# 1203_05.net
KiCad netlist of a schematic drawn in EAGLE
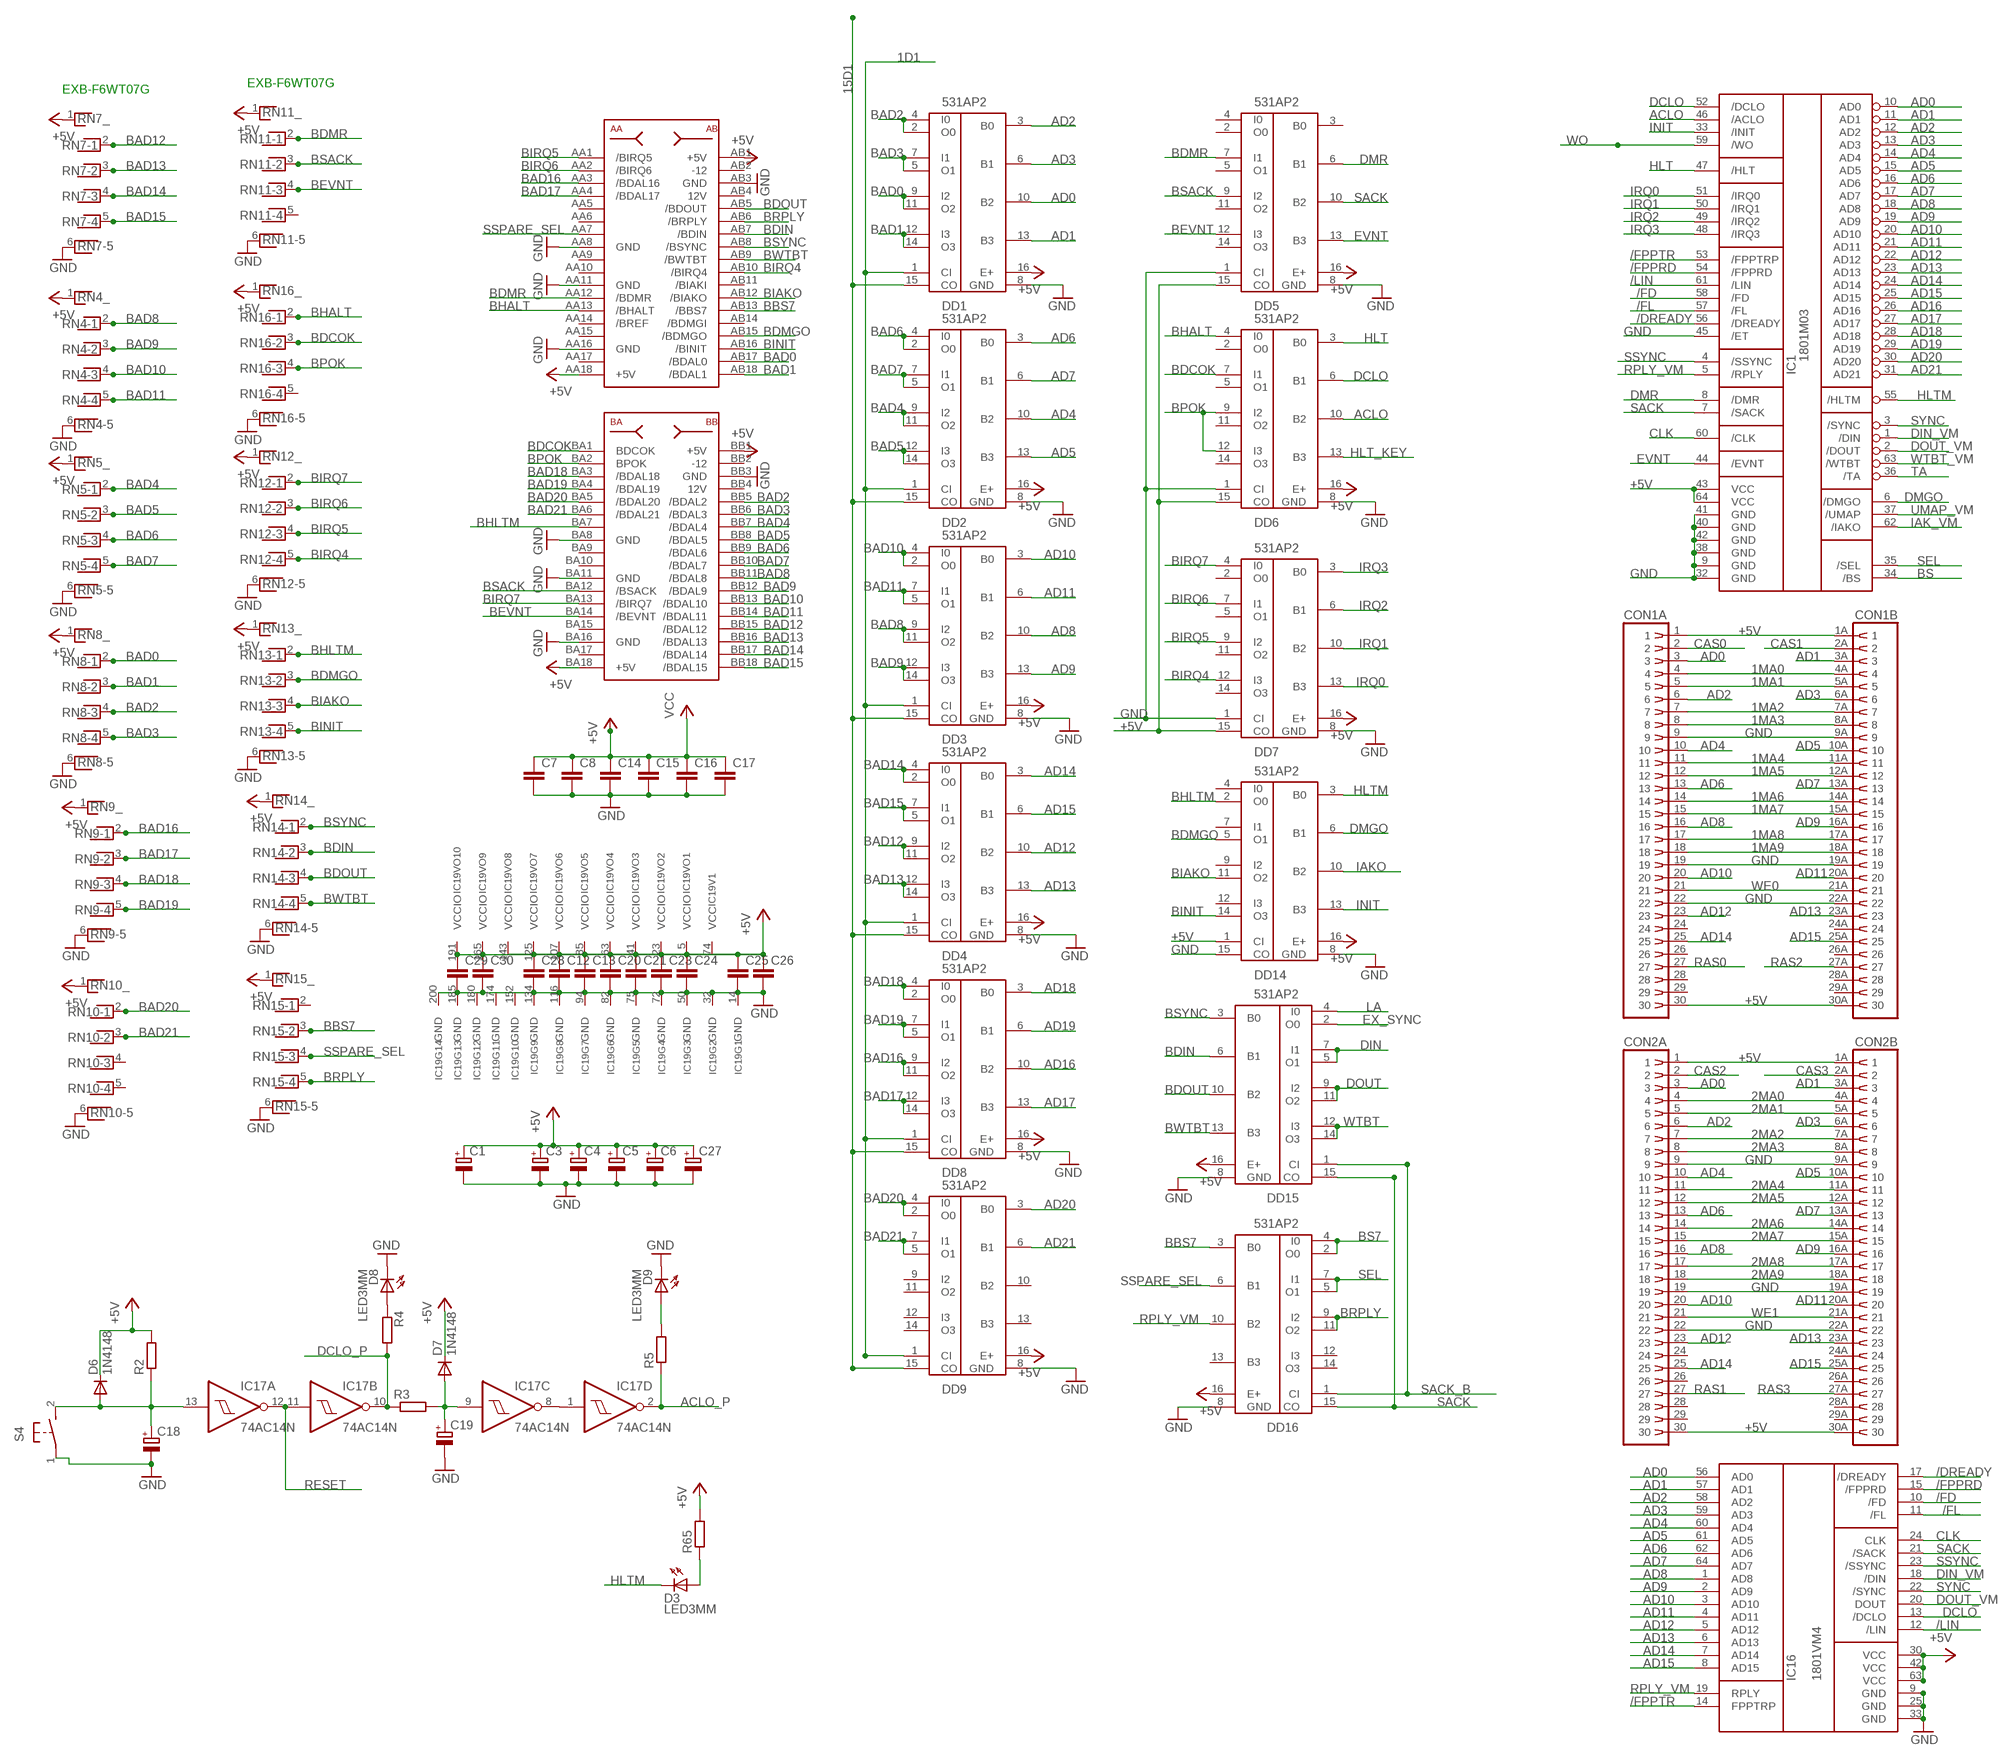
[diagram p0: schematic, sheet 1, part 1 of 2]
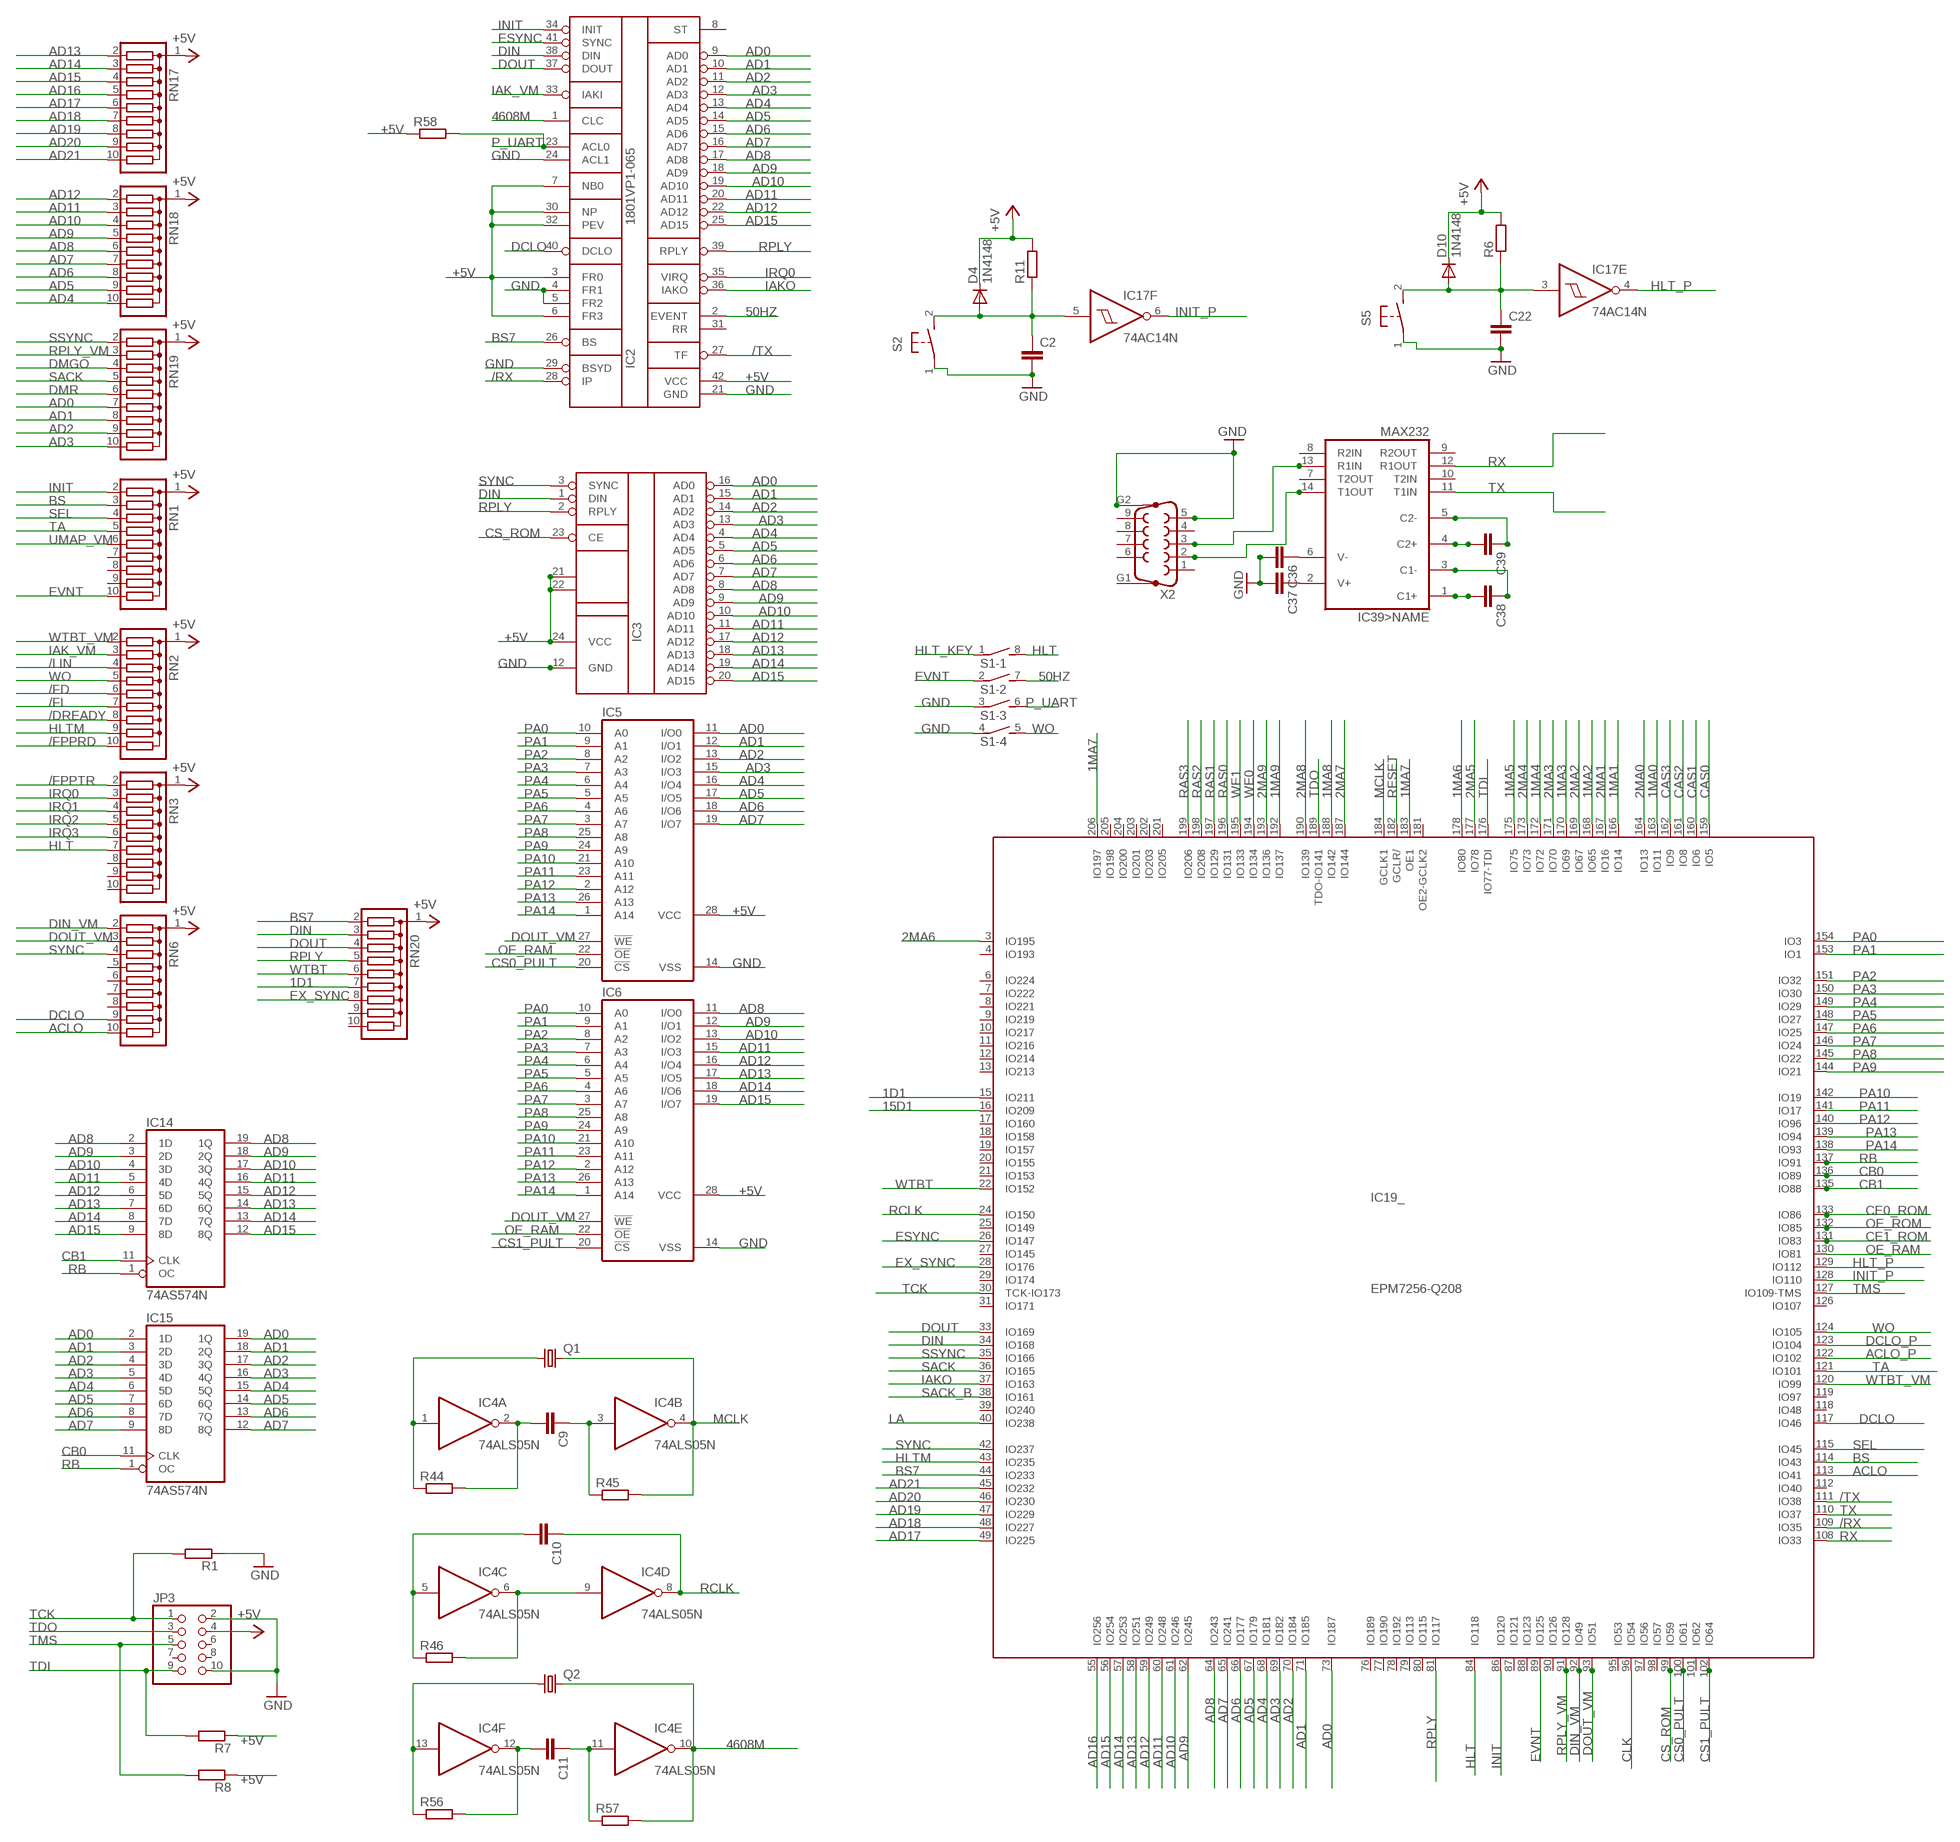
[diagram p1: schematic, sheet 1, part 2 of 2]

(export (version "E")
  (design (tool "Eeschema 10.0.6"))
  (components
    (comp (ref "C1")
      (value "CPOL-EUCT6032")
      (footprint "eagle-import:CT6032")
      (libsource (lib "eagle-import") (part "CPOL-EUCT6032"))
    )
    (comp (ref "C2")
      (value "C-EU050-024X044")
      (footprint "eagle-import:C050-024X044")
      (libsource (lib "eagle-import") (part "C-EU050-024X044"))
    )
    (comp (ref "C3")
      (value "CPOL-EUCT6032")
      (footprint "eagle-import:CT6032")
      (libsource (lib "eagle-import") (part "CPOL-EUCT6032"))
    )
    (comp (ref "C4")
      (value "CPOL-EUCT6032")
      (footprint "eagle-import:CT6032")
      (libsource (lib "eagle-import") (part "CPOL-EUCT6032"))
    )
    (comp (ref "C5")
      (value "CPOL-EUB45181A")
      (footprint "eagle-import:B45181A")
      (libsource (lib "eagle-import") (part "CPOL-EUB45181A"))
    )
    (comp (ref "C6")
      (value "CPOL-EUCT6032")
      (footprint "eagle-import:CT6032")
      (libsource (lib "eagle-import") (part "CPOL-EUCT6032"))
    )
    (comp (ref "C7")
      (value "C-EU050-024X044")
      (footprint "eagle-import:C050-024X044")
      (libsource (lib "eagle-import") (part "C-EU050-024X044"))
    )
    (comp (ref "C8")
      (value "C-EU050-024X044")
      (footprint "eagle-import:C050-024X044")
      (libsource (lib "eagle-import") (part "C-EU050-024X044"))
    )
    (comp (ref "C9")
      (value "C-EUC0805")
      (footprint "eagle-import:C0805")
      (libsource (lib "eagle-import") (part "C-EUC0805"))
    )
    (comp (ref "C10")
      (value "C-EU025-024X044")
      (footprint "eagle-import:C025-024X044")
      (libsource (lib "eagle-import") (part "C-EU025-024X044"))
    )
    (comp (ref "C11")
      (value "C-EUC0805")
      (footprint "eagle-import:C0805")
      (libsource (lib "eagle-import") (part "C-EUC0805"))
    )
    (comp (ref "C12")
      (value "C-EUC0805")
      (footprint "eagle-import:C0805")
      (libsource (lib "eagle-import") (part "C-EUC0805"))
    )
    (comp (ref "C13")
      (value "C-EUC0805")
      (footprint "eagle-import:C0805")
      (libsource (lib "eagle-import") (part "C-EUC0805"))
    )
    (comp (ref "C14")
      (value "C-EU050-024X044")
      (footprint "eagle-import:C050-024X044")
      (libsource (lib "eagle-import") (part "C-EU050-024X044"))
    )
    (comp (ref "C15")
      (value "C-EU050-024X044")
      (footprint "eagle-import:C050-024X044")
      (libsource (lib "eagle-import") (part "C-EU050-024X044"))
    )
    (comp (ref "C16")
      (value "C-EU050-024X044")
      (footprint "eagle-import:C050-024X044")
      (libsource (lib "eagle-import") (part "C-EU050-024X044"))
    )
    (comp (ref "C17")
      (value "C-EU050-024X044")
      (footprint "eagle-import:C050-024X044")
      (libsource (lib "eagle-import") (part "C-EU050-024X044"))
    )
    (comp (ref "C18")
      (value "CPOL-EUE2.5-5")
      (footprint "eagle-import:E2,5-5")
      (libsource (lib "eagle-import") (part "CPOL-EUE2.5-5"))
    )
    (comp (ref "C19")
      (value "CPOL-EUE2.5-5")
      (footprint "eagle-import:E2,5-5")
      (libsource (lib "eagle-import") (part "CPOL-EUE2.5-5"))
    )
    (comp (ref "C20")
      (value "C-EUC0805")
      (footprint "eagle-import:C0805")
      (libsource (lib "eagle-import") (part "C-EUC0805"))
    )
    (comp (ref "C21")
      (value "C-EUC0805")
      (footprint "eagle-import:C0805")
      (libsource (lib "eagle-import") (part "C-EUC0805"))
    )
    (comp (ref "C22")
      (value "C-EU050-024X044")
      (footprint "eagle-import:C050-024X044")
      (libsource (lib "eagle-import") (part "C-EU050-024X044"))
    )
    (comp (ref "C23")
      (value "C-EU050-024X044")
      (footprint "eagle-import:C050-024X044")
      (libsource (lib "eagle-import") (part "C-EU050-024X044"))
    )
    (comp (ref "C24")
      (value "C-EU050-024X044")
      (footprint "eagle-import:C050-024X044")
      (libsource (lib "eagle-import") (part "C-EU050-024X044"))
    )
    (comp (ref "C25")
      (value "C-EU050-024X044")
      (footprint "eagle-import:C050-024X044")
      (libsource (lib "eagle-import") (part "C-EU050-024X044"))
    )
    (comp (ref "C26")
      (value "C-EU050-024X044")
      (footprint "eagle-import:C050-024X044")
      (libsource (lib "eagle-import") (part "C-EU050-024X044"))
    )
    (comp (ref "C27")
      (value "CPOL-EUCT6032")
      (footprint "eagle-import:CT6032")
      (libsource (lib "eagle-import") (part "CPOL-EUCT6032"))
    )
    (comp (ref "C28")
      (value "C-EU050-024X044")
      (footprint "eagle-import:C050-024X044")
      (libsource (lib "eagle-import") (part "C-EU050-024X044"))
    )
    (comp (ref "C29")
      (value "C-EU050-024X044")
      (footprint "eagle-import:C050-024X044")
      (libsource (lib "eagle-import") (part "C-EU050-024X044"))
    )
    (comp (ref "C30")
      (value "C-EU050-024X044")
      (footprint "eagle-import:C050-024X044")
      (libsource (lib "eagle-import") (part "C-EU050-024X044"))
    )
    (comp (ref "C36")
      (value "C-EU025-024X044")
      (footprint "eagle-import:C025-024X044")
      (libsource (lib "eagle-import") (part "C-EU025-024X044"))
    )
    (comp (ref "C37")
      (value "C-EU025-024X044")
      (footprint "eagle-import:C025-024X044")
      (libsource (lib "eagle-import") (part "C-EU025-024X044"))
    )
    (comp (ref "C38")
      (value "C-EU025-024X044")
      (footprint "eagle-import:C025-024X044")
      (libsource (lib "eagle-import") (part "C-EU025-024X044"))
    )
    (comp (ref "C39")
      (value "C-EU025-024X044")
      (footprint "eagle-import:C025-024X044")
      (libsource (lib "eagle-import") (part "C-EU025-024X044"))
    )
    (comp (ref "CON1")
      (value "SIMM30-2")
      (footprint "eagle-import:SIMM30-2")
      (libsource (lib "eagle-import") (part "SIMM30-2"))
    )
    (comp (ref "CON2")
      (value "SIMM30-2")
      (footprint "eagle-import:SIMM30-2")
      (libsource (lib "eagle-import") (part "SIMM30-2"))
    )
    (comp (ref "D3")
      (value "LED3MM")
      (footprint "eagle-import:LED3MM")
      (libsource (lib "eagle-import") (part "LED3MM"))
    )
    (comp (ref "D4")
      (value "1N4148")
      (footprint "eagle-import:DO35-10")
      (libsource (lib "eagle-import") (part "1N4148"))
    )
    (comp (ref "D6")
      (value "1N4148")
      (footprint "eagle-import:DO35-10")
      (libsource (lib "eagle-import") (part "1N4148"))
    )
    (comp (ref "D7")
      (value "1N4148")
      (footprint "eagle-import:DO35-10")
      (libsource (lib "eagle-import") (part "1N4148"))
    )
    (comp (ref "D8")
      (value "LED3MM")
      (footprint "eagle-import:LED3MM")
      (libsource (lib "eagle-import") (part "LED3MM"))
    )
    (comp (ref "D9")
      (value "LED3MM")
      (footprint "eagle-import:LED3MM")
      (libsource (lib "eagle-import") (part "LED3MM"))
    )
    (comp (ref "D10")
      (value "1N4148")
      (footprint "eagle-import:DO35-10")
      (libsource (lib "eagle-import") (part "1N4148"))
    )
    (comp (ref "DD1")
      (value "531AP2")
      (footprint "eagle-import:DIL16")
      (libsource (lib "eagle-import") (part "531AP2"))
    )
    (comp (ref "DD2")
      (value "531AP2")
      (footprint "eagle-import:DIL16")
      (libsource (lib "eagle-import") (part "531AP2"))
    )
    (comp (ref "DD3")
      (value "531AP2")
      (footprint "eagle-import:DIL16")
      (libsource (lib "eagle-import") (part "531AP2"))
    )
    (comp (ref "DD4")
      (value "531AP2")
      (footprint "eagle-import:DIL16")
      (libsource (lib "eagle-import") (part "531AP2"))
    )
    (comp (ref "DD5")
      (value "531AP2")
      (footprint "eagle-import:DIL16")
      (libsource (lib "eagle-import") (part "531AP2"))
    )
    (comp (ref "DD6")
      (value "531AP2")
      (footprint "eagle-import:DIL16")
      (libsource (lib "eagle-import") (part "531AP2"))
    )
    (comp (ref "DD7")
      (value "531AP2")
      (footprint "eagle-import:DIL16")
      (libsource (lib "eagle-import") (part "531AP2"))
    )
    (comp (ref "DD8")
      (value "531AP2")
      (footprint "eagle-import:DIL16")
      (libsource (lib "eagle-import") (part "531AP2"))
    )
    (comp (ref "DD9")
      (value "531AP2")
      (footprint "eagle-import:DIL16")
      (libsource (lib "eagle-import") (part "531AP2"))
    )
    (comp (ref "DD14")
      (value "531AP2")
      (footprint "eagle-import:DIL16")
      (libsource (lib "eagle-import") (part "531AP2"))
    )
    (comp (ref "DD15")
      (value "531AP2")
      (footprint "eagle-import:DIL16")
      (libsource (lib "eagle-import") (part "531AP2"))
    )
    (comp (ref "DD16")
      (value "531AP2")
      (footprint "eagle-import:DIL16")
      (libsource (lib "eagle-import") (part "531AP2"))
    )
    (comp (ref "IC1")
      (value "1801M03")
      (footprint "eagle-import:DIL64")
      (libsource (lib "eagle-import") (part "1801M03"))
    )
    (comp (ref "IC2")
      (value "1801VP1-065")
      (footprint "eagle-import:1801")
      (libsource (lib "eagle-import") (part "1801VP1-065"))
    )
    (comp (ref "IC3")
      (value "1801RE2")
      (footprint "eagle-import:DIL24")
      (libsource (lib "eagle-import") (part "1801RE2"))
    )
    (comp (ref "IC4")
      (value "74ALS05N")
      (footprint "eagle-import:DIL14")
      (libsource (lib "eagle-import") (part "7405NALS"))
    )
    (comp (ref "IC5")
      (value "62832P")
      (footprint "eagle-import:DIL28-3")
      (libsource (lib "eagle-import") (part "62832P"))
    )
    (comp (ref "IC6")
      (value "62832P")
      (footprint "eagle-import:DIL28-3")
      (libsource (lib "eagle-import") (part "62832P"))
    )
    (comp (ref "IC14")
      (value "74AS574N")
      (footprint "eagle-import:DIL20")
      (libsource (lib "eagle-import") (part "74574NAS"))
    )
    (comp (ref "IC15")
      (value "74AS574N")
      (footprint "eagle-import:DIL20")
      (libsource (lib "eagle-import") (part "74574NAS"))
    )
    (comp (ref "IC16")
      (value "1801VM4")
      (footprint "eagle-import:1801VM4")
      (libsource (lib "eagle-import") (part "1801VM4"))
    )
    (comp (ref "IC17")
      (value "74AC14N")
      (footprint "eagle-import:DIL14")
      (libsource (lib "eagle-import") (part "7414NAC"))
    )
    (comp (ref "IC19")
      (value "EPM7256-Q208")
      (footprint "eagle-import:RQFP208")
      (fields (field (name "MPN") "EPM7256AEQC208-10N"))
      (libsource (lib "eagle-import") (part "EPM7256-Q208"))
    )
    (comp (ref "IC39")
      (value "MAX232")
      (footprint "eagle-import:DIL16")
      (libsource (lib "eagle-import") (part "MAX232"))
    )
    (comp (ref "JP3")
      (value "PINHD-2X5")
      (footprint "eagle-import:2X05")
      (libsource (lib "eagle-import") (part "PINHD-2X5"))
    )
    (comp (ref "Q1")
      (value "HC49U70")
      (footprint "eagle-import:HC49U70")
      (libsource (lib "eagle-import") (part "HC49U70"))
    )
    (comp (ref "Q2")
      (value "HC49U70")
      (footprint "eagle-import:HC49U70")
      (libsource (lib "eagle-import") (part "HC49U70"))
    )
    (comp (ref "R1")
      (value "R-EU_M0805")
      (footprint "eagle-import:M0805")
      (libsource (lib "eagle-import") (part "R-EU_M0805"))
    )
    (comp (ref "R2")
      (value "R-EU_0207/10")
      (footprint "eagle-import:0207_10")
      (libsource (lib "eagle-import") (part "R-EU_0207/10"))
    )
    (comp (ref "R3")
      (value "R-EU_0207/10")
      (footprint "eagle-import:0207_10")
      (libsource (lib "eagle-import") (part "R-EU_0207/10"))
    )
    (comp (ref "R4")
      (value "R-EU_M0805")
      (footprint "eagle-import:M0805")
      (libsource (lib "eagle-import") (part "R-EU_M0805"))
    )
    (comp (ref "R5")
      (value "R-EU_M0805")
      (footprint "eagle-import:M0805")
      (libsource (lib "eagle-import") (part "R-EU_M0805"))
    )
    (comp (ref "R6")
      (value "R-EU_0207/10")
      (footprint "eagle-import:0207_10")
      (libsource (lib "eagle-import") (part "R-EU_0207/10"))
    )
    (comp (ref "R7")
      (value "R-EU_M0805")
      (footprint "eagle-import:M0805")
      (libsource (lib "eagle-import") (part "R-EU_M0805"))
    )
    (comp (ref "R8")
      (value "R-EU_M0805")
      (footprint "eagle-import:M0805")
      (libsource (lib "eagle-import") (part "R-EU_M0805"))
    )
    (comp (ref "R11")
      (value "R-EU_0207/10")
      (footprint "eagle-import:0207_10")
      (libsource (lib "eagle-import") (part "R-EU_0207/10"))
    )
    (comp (ref "R44")
      (value "R-EU_M0805")
      (footprint "eagle-import:M0805")
      (libsource (lib "eagle-import") (part "R-EU_M0805"))
    )
    (comp (ref "R45")
      (value "R-EU_M0805")
      (footprint "eagle-import:M0805")
      (libsource (lib "eagle-import") (part "R-EU_M0805"))
    )
    (comp (ref "R46")
      (value "R-EU_0207/10")
      (footprint "eagle-import:0207_10")
      (libsource (lib "eagle-import") (part "R-EU_0207/10"))
    )
    (comp (ref "R56")
      (value "R-EU_M0805")
      (footprint "eagle-import:M0805")
      (libsource (lib "eagle-import") (part "R-EU_M0805"))
    )
    (comp (ref "R57")
      (value "R-EU_M0805")
      (footprint "eagle-import:M0805")
      (libsource (lib "eagle-import") (part "R-EU_M0805"))
    )
    (comp (ref "R58")
      (value "R-EU_0207/10")
      (footprint "eagle-import:0207_10")
      (libsource (lib "eagle-import") (part "R-EU_0207/10"))
    )
    (comp (ref "R65")
      (value "R-EU_M0805")
      (footprint "eagle-import:M0805")
      (libsource (lib "eagle-import") (part "R-EU_M0805"))
    )
    (comp (ref "RN1")
      (value "G09R")
      (footprint "eagle-import:SIL10")
      (libsource (lib "eagle-import") (part "G09R"))
    )
    (comp (ref "RN2")
      (value "G09R")
      (footprint "eagle-import:SIL10")
      (libsource (lib "eagle-import") (part "G09R"))
    )
    (comp (ref "RN3")
      (value "G09R")
      (footprint "eagle-import:SIL10")
      (libsource (lib "eagle-import") (part "G09R"))
    )
    (comp (ref "RN4")
      (value "RNX5")
      (footprint "eagle-import:RN-6")
      (libsource (lib "eagle-import") (part "RNX5"))
    )
    (comp (ref "RN5")
      (value "RNX5")
      (footprint "eagle-import:RN-6")
      (libsource (lib "eagle-import") (part "RNX5"))
    )
    (comp (ref "RN6")
      (value "G09R")
      (footprint "eagle-import:SIL10")
      (libsource (lib "eagle-import") (part "G09R"))
    )
    (comp (ref "RN7")
      (value "RNX5")
      (footprint "eagle-import:RN-6")
      (libsource (lib "eagle-import") (part "RNX5"))
    )
    (comp (ref "RN8")
      (value "RNX5")
      (footprint "eagle-import:RN-6")
      (libsource (lib "eagle-import") (part "RNX5"))
    )
    (comp (ref "RN9")
      (value "RNX5")
      (footprint "eagle-import:RN-6")
      (libsource (lib "eagle-import") (part "RNX5"))
    )
    (comp (ref "RN10")
      (value "RNX5")
      (footprint "eagle-import:RN-6")
      (libsource (lib "eagle-import") (part "RNX5"))
    )
    (comp (ref "RN11")
      (value "RNX5")
      (footprint "eagle-import:RN-6")
      (libsource (lib "eagle-import") (part "RNX5"))
    )
    (comp (ref "RN12")
      (value "RNX5")
      (footprint "eagle-import:RN-6")
      (libsource (lib "eagle-import") (part "RNX5"))
    )
    (comp (ref "RN13")
      (value "RNX5")
      (footprint "eagle-import:RN-6")
      (libsource (lib "eagle-import") (part "RNX5"))
    )
    (comp (ref "RN14")
      (value "RNX5")
      (footprint "eagle-import:RN-6")
      (libsource (lib "eagle-import") (part "RNX5"))
    )
    (comp (ref "RN15")
      (value "RNX5")
      (footprint "eagle-import:RN-6")
      (libsource (lib "eagle-import") (part "RNX5"))
    )
    (comp (ref "RN16")
      (value "RNX5")
      (footprint "eagle-import:RN-6")
      (libsource (lib "eagle-import") (part "RNX5"))
    )
    (comp (ref "RN17")
      (value "G09R")
      (footprint "eagle-import:SIL10")
      (libsource (lib "eagle-import") (part "G09R"))
    )
    (comp (ref "RN18")
      (value "G09R")
      (footprint "eagle-import:SIL10")
      (libsource (lib "eagle-import") (part "G09R"))
    )
    (comp (ref "RN19")
      (value "G09R")
      (footprint "eagle-import:SIL10")
      (libsource (lib "eagle-import") (part "G09R"))
    )
    (comp (ref "RN20")
      (value "G09R")
      (footprint "eagle-import:SIL10")
      (libsource (lib "eagle-import") (part "G09R"))
    )
    (comp (ref "S1")
      (value "DIP04SB")
      (footprint "eagle-import:DIP04SB")
      (libsource (lib "eagle-import") (part "DIP04SB"))
    )
    (comp (ref "S2")
      (value "31-XX")
      (footprint "eagle-import:B3F-31XX")
      (libsource (lib "eagle-import") (part "31-XX"))
    )
    (comp (ref "S4")
      (value "31-XX")
      (footprint "eagle-import:B3F-31XX")
      (libsource (lib "eagle-import") (part "31-XX"))
    )
    (comp (ref "S5")
      (value "31-XX")
      (footprint "eagle-import:B3F-31XX")
      (libsource (lib "eagle-import") (part "31-XX"))
    )
    (comp (ref "X2")
      (value "F09HP")
      (footprint "eagle-import:F09HP")
      (libsource (lib "eagle-import") (part "F09HP"))
    )
    (comp (ref "XP1")
      (value "CON1")
      (footprint "eagle-import:CON1")
      (libsource (lib "eagle-import") (part "CON1"))
    )
  )
  (nets
    (net (code "1") (name "+5V") (class "Default")
      (node (ref "C1") (pin "+") (pinfunction "+_+") (pintype "passive"))
      (node (ref "C12") (pin "1") (pinfunction "1_1") (pintype "passive"))
      (node (ref "C13") (pin "1") (pinfunction "1_1") (pintype "passive"))
      (node (ref "C14") (pin "1") (pinfunction "1_1") (pintype "passive"))
      (node (ref "C15") (pin "1") (pinfunction "1_1") (pintype "passive"))
      (node (ref "C16") (pin "1") (pinfunction "1_1") (pintype "passive"))
      (node (ref "C17") (pin "1") (pinfunction "1_1") (pintype "passive"))
      (node (ref "C20") (pin "1") (pinfunction "1_1") (pintype "passive"))
      (node (ref "C21") (pin "1") (pinfunction "1_1") (pintype "passive"))
      (node (ref "C23") (pin "1") (pinfunction "1_1") (pintype "passive"))
      (node (ref "C24") (pin "1") (pinfunction "1_1") (pintype "passive"))
      (node (ref "C25") (pin "1") (pinfunction "1_1") (pintype "passive"))
      (node (ref "C26") (pin "1") (pinfunction "1_1") (pintype "passive"))
      (node (ref "C27") (pin "+") (pinfunction "+_+") (pintype "passive"))
      (node (ref "C28") (pin "1") (pinfunction "1_1") (pintype "passive"))
      (node (ref "C29") (pin "1") (pinfunction "1_1") (pintype "passive"))
      (node (ref "C3") (pin "+") (pinfunction "+_+") (pintype "passive"))
      (node (ref "C30") (pin "1") (pinfunction "1_1") (pintype "passive"))
      (node (ref "C4") (pin "+") (pinfunction "+_+") (pintype "passive"))
      (node (ref "C5") (pin "+") (pinfunction "+_+") (pintype "passive"))
      (node (ref "C6") (pin "+") (pinfunction "+_+") (pintype "passive"))
      (node (ref "C7") (pin "1") (pinfunction "1_1") (pintype "passive"))
      (node (ref "C8") (pin "1") (pinfunction "1_1") (pintype "passive"))
      (node (ref "CON1") (pin "1") (pinfunction "1_1") (pintype "passive"))
      (node (ref "CON1") (pin "1A") (pinfunction "1_1A") (pintype "passive"))
      (node (ref "CON1") (pin "30") (pinfunction "30_30") (pintype "passive"))
      (node (ref "CON1") (pin "30A") (pinfunction "30_30A") (pintype "passive"))
      (node (ref "CON2") (pin "1") (pinfunction "1_1") (pintype "passive"))
      (node (ref "CON2") (pin "1A") (pinfunction "1_1A") (pintype "passive"))
      (node (ref "CON2") (pin "30") (pinfunction "30_30") (pintype "passive"))
      (node (ref "CON2") (pin "30A") (pinfunction "30_30A") (pintype "passive"))
      (node (ref "D10") (pin "K") (pinfunction "C_K") (pintype "passive"))
      (node (ref "D4") (pin "K") (pinfunction "C_K") (pintype "passive"))
      (node (ref "D6") (pin "K") (pinfunction "C_K") (pintype "passive"))
      (node (ref "D7") (pin "K") (pinfunction "C_K") (pintype "passive"))
      (node (ref "DD1") (pin "16") (pinfunction "E+_16") (pintype "bidirectional"))
      (node (ref "DD14") (pin "1") (pinfunction "CI_1") (pintype "bidirectional"))
      (node (ref "DD14") (pin "16") (pinfunction "E+_16") (pintype "bidirectional"))
      (node (ref "DD15") (pin "16") (pinfunction "E+_16") (pintype "bidirectional"))
      (node (ref "DD16") (pin "16") (pinfunction "E+_16") (pintype "bidirectional"))
      (node (ref "DD2") (pin "16") (pinfunction "E+_16") (pintype "bidirectional"))
      (node (ref "DD3") (pin "16") (pinfunction "E+_16") (pintype "bidirectional"))
      (node (ref "DD4") (pin "16") (pinfunction "E+_16") (pintype "bidirectional"))
      (node (ref "DD5") (pin "15") (pinfunction "CO_15") (pintype "bidirectional"))
      (node (ref "DD5") (pin "16") (pinfunction "E+_16") (pintype "bidirectional"))
      (node (ref "DD6") (pin "15") (pinfunction "CO_15") (pintype "bidirectional"))
      (node (ref "DD6") (pin "16") (pinfunction "E+_16") (pintype "bidirectional"))
      (node (ref "DD7") (pin "15") (pinfunction "CO_15") (pintype "bidirectional"))
      (node (ref "DD7") (pin "16") (pinfunction "E+_16") (pintype "bidirectional"))
      (node (ref "DD8") (pin "16") (pinfunction "E+_16") (pintype "bidirectional"))
      (node (ref "DD9") (pin "16") (pinfunction "E+_16") (pintype "bidirectional"))
      (node (ref "IC1") (pin "43") (pinfunction "VCC_43") (pintype "bidirectional"))
      (node (ref "IC1") (pin "64") (pinfunction "VCC_64") (pintype "bidirectional"))
      (node (ref "IC16") (pin "30") (pinfunction "VCC_30") (pintype "bidirectional"))
      (node (ref "IC16") (pin "42") (pinfunction "VCC_42") (pintype "bidirectional"))
      (node (ref "IC16") (pin "63") (pinfunction "VCC_63") (pintype "bidirectional"))
      (node (ref "IC19") (pin "107") (pinfunction "VCCIO_107") (pintype "power_in"))
      (node (ref "IC19") (pin "125") (pinfunction "VCCIO_125") (pintype "power_in"))
      (node (ref "IC19") (pin "143") (pinfunction "VCCIO_143") (pintype "power_in"))
      (node (ref "IC19") (pin "165") (pinfunction "VCCIO_165") (pintype "power_in"))
      (node (ref "IC19") (pin "191") (pinfunction "VCCIO_191") (pintype "power_in"))
      (node (ref "IC19") (pin "23") (pinfunction "VCCIO_23") (pintype "power_in"))
      (node (ref "IC19") (pin "41") (pinfunction "VCCIO_41") (pintype "power_in"))
      (node (ref "IC19") (pin "5") (pinfunction "VCCIO_5") (pintype "power_in"))
      (node (ref "IC19") (pin "63") (pinfunction "VCCIO_63") (pintype "power_in"))
      (node (ref "IC19") (pin "74") (pinfunction "VCC_74") (pintype "power_in"))
      (node (ref "IC19") (pin "85") (pinfunction "VCCIO_85") (pintype "power_in"))
      (node (ref "IC2") (pin "3") (pinfunction "FR0_3") (pintype "bidirectional"))
      (node (ref "IC2") (pin "30") (pinfunction "NP_30") (pintype "bidirectional"))
      (node (ref "IC2") (pin "32") (pinfunction "PEV_32") (pintype "bidirectional"))
      (node (ref "IC2") (pin "42") (pinfunction "VCC_42") (pintype "bidirectional"))
      (node (ref "IC2") (pin "6") (pinfunction "FR3_6") (pintype "bidirectional"))
      (node (ref "IC2") (pin "7") (pinfunction "NB0_7") (pintype "bidirectional"))
      (node (ref "IC3") (pin "21") (pinfunction "F0_21") (pintype "bidirectional"))
      (node (ref "IC3") (pin "22") (pinfunction "F1_22") (pintype "bidirectional"))
      (node (ref "IC3") (pin "24") (pinfunction "VCC_24") (pintype "bidirectional"))
      (node (ref "IC5") (pin "28") (pinfunction "VCC_28") (pintype "power_in"))
      (node (ref "IC6") (pin "28") (pinfunction "VCC_28") (pintype "power_in"))
      (node (ref "JP3") (pin "4") (pinfunction "4_4") (pintype "passive"))
      (node (ref "R11") (pin "2") (pinfunction "2_2") (pintype "passive"))
      (node (ref "R2") (pin "2") (pinfunction "2_2") (pintype "passive"))
      (node (ref "R58") (pin "1") (pinfunction "1_1") (pintype "passive"))
      (node (ref "R6") (pin "2") (pinfunction "2_2") (pintype "passive"))
      (node (ref "R65") (pin "2") (pinfunction "2_2") (pintype "passive"))
      (node (ref "R7") (pin "1") (pinfunction "1_1") (pintype "passive"))
      (node (ref "R8") (pin "1") (pinfunction "1_1") (pintype "passive"))
      (node (ref "RN1") (pin "1") (pinfunction "1_1") (pintype "passive"))
      (node (ref "RN10") (pin "1") (pinfunction "1_1") (pintype "passive"))
      (node (ref "RN11") (pin "1") (pinfunction "1_1") (pintype "passive"))
      (node (ref "RN12") (pin "1") (pinfunction "1_1") (pintype "passive"))
      (node (ref "RN13") (pin "1") (pinfunction "1_1") (pintype "passive"))
      (node (ref "RN14") (pin "1") (pinfunction "1_1") (pintype "passive"))
      (node (ref "RN15") (pin "1") (pinfunction "1_1") (pintype "passive"))
      (node (ref "RN16") (pin "1") (pinfunction "1_1") (pintype "passive"))
      (node (ref "RN17") (pin "1") (pinfunction "1_1") (pintype "passive"))
      (node (ref "RN18") (pin "1") (pinfunction "1_1") (pintype "passive"))
      (node (ref "RN19") (pin "1") (pinfunction "1_1") (pintype "passive"))
      (node (ref "RN2") (pin "1") (pinfunction "1_1") (pintype "passive"))
      (node (ref "RN20") (pin "1") (pinfunction "1_1") (pintype "passive"))
      (node (ref "RN3") (pin "1") (pinfunction "1_1") (pintype "passive"))
      (node (ref "RN4") (pin "1") (pinfunction "1_1") (pintype "passive"))
      (node (ref "RN5") (pin "1") (pinfunction "1_1") (pintype "passive"))
      (node (ref "RN6") (pin "1") (pinfunction "1_1") (pintype "passive"))
      (node (ref "RN7") (pin "1") (pinfunction "1_1") (pintype "passive"))
      (node (ref "RN8") (pin "1") (pinfunction "1_1") (pintype "passive"))
      (node (ref "RN9") (pin "1") (pinfunction "1_1") (pintype "passive"))
      (node (ref "XP1") (pin "AA18") (pinfunction "+5V_AA18") (pintype "bidirectional"))
      (node (ref "XP1") (pin "AB1") (pinfunction "+5V_AB1") (pintype "bidirectional"))
      (node (ref "XP1") (pin "BA18") (pinfunction "+5V_BA18") (pintype "bidirectional"))
      (node (ref "XP1") (pin "BB1") (pinfunction "+5V_BB1") (pintype "bidirectional"))
    )
    (net (code "2") (name "/1D1") (class "Default")
      (node (ref "DD1") (pin "1") (pinfunction "CI_1") (pintype "bidirectional"))
      (node (ref "DD2") (pin "1") (pinfunction "CI_1") (pintype "bidirectional"))
      (node (ref "DD3") (pin "1") (pinfunction "CI_1") (pintype "bidirectional"))
      (node (ref "DD4") (pin "1") (pinfunction "CI_1") (pintype "bidirectional"))
      (node (ref "DD8") (pin "1") (pinfunction "CI_1") (pintype "bidirectional"))
      (node (ref "DD9") (pin "1") (pinfunction "CI_1") (pintype "bidirectional"))
      (node (ref "IC19") (pin "15") (pinfunction "IO211_15") (pintype "bidirectional"))
      (node (ref "RN20") (pin "7") (pinfunction "7_7") (pintype "passive"))
    )
    (net (code "3") (name "/1MA0") (class "Default")
      (node (ref "CON1") (pin "4") (pinfunction "4_4") (pintype "passive"))
      (node (ref "CON1") (pin "4A") (pinfunction "4_4A") (pintype "passive"))
      (node (ref "IC19") (pin "163") (pinfunction "IO11_163") (pintype "bidirectional"))
    )
    (net (code "4") (name "/1MA1") (class "Default")
      (node (ref "CON1") (pin "5") (pinfunction "5_5") (pintype "passive"))
      (node (ref "CON1") (pin "5A") (pinfunction "5_5A") (pintype "passive"))
      (node (ref "IC19") (pin "166") (pinfunction "IO14_166") (pintype "bidirectional"))
    )
    (net (code "5") (name "/1MA2") (class "Default")
      (node (ref "CON1") (pin "7") (pinfunction "7_7") (pintype "passive"))
      (node (ref "CON1") (pin "7A") (pinfunction "7_7A") (pintype "passive"))
      (node (ref "IC19") (pin "168") (pinfunction "IO65_168") (pintype "bidirectional"))
    )
    (net (code "6") (name "/1MA3") (class "Default")
      (node (ref "CON1") (pin "8") (pinfunction "8_8") (pintype "passive"))
      (node (ref "CON1") (pin "8A") (pinfunction "8_8A") (pintype "passive"))
      (node (ref "IC19") (pin "170") (pinfunction "IO69_170") (pintype "bidirectional"))
    )
    (net (code "7") (name "/1MA4") (class "Default")
      (node (ref "CON1") (pin "11") (pinfunction "11_11") (pintype "passive"))
      (node (ref "CON1") (pin "11A") (pinfunction "11_11A") (pintype "passive"))
      (node (ref "IC19") (pin "172") (pinfunction "IO72_172") (pintype "bidirectional"))
    )
    (net (code "8") (name "/1MA5") (class "Default")
      (node (ref "CON1") (pin "12") (pinfunction "12_12") (pintype "passive"))
      (node (ref "CON1") (pin "12A") (pinfunction "12_12A") (pintype "passive"))
      (node (ref "IC19") (pin "175") (pinfunction "IO75_175") (pintype "bidirectional"))
    )
    (net (code "9") (name "/1MA6") (class "Default")
      (node (ref "CON1") (pin "14") (pinfunction "14_14") (pintype "passive"))
      (node (ref "CON1") (pin "14A") (pinfunction "14_14A") (pintype "passive"))
      (node (ref "IC19") (pin "178") (pinfunction "IO80_178") (pintype "bidirectional"))
    )
    (net (code "10") (name "/1MA7") (class "Default")
      (node (ref "CON1") (pin "15") (pinfunction "15_15") (pintype "passive"))
      (node (ref "CON1") (pin "15A") (pinfunction "15_15A") (pintype "passive"))
      (node (ref "IC19") (pin "183") (pinfunction "OE1_183") (pintype "input"))
      (node (ref "IC19") (pin "206") (pinfunction "IO197_206") (pintype "bidirectional"))
    )
    (net (code "11") (name "/1MA8") (class "Default")
      (node (ref "CON1") (pin "17") (pinfunction "17_17") (pintype "passive"))
      (node (ref "CON1") (pin "17A") (pinfunction "17_17A") (pintype "passive"))
      (node (ref "IC19") (pin "188") (pinfunction "IO142_188") (pintype "bidirectional"))
    )
    (net (code "12") (name "/1MA9") (class "Default")
      (node (ref "CON1") (pin "18") (pinfunction "18_18") (pintype "passive"))
      (node (ref "CON1") (pin "18A") (pinfunction "18_18A") (pintype "passive"))
      (node (ref "IC19") (pin "192") (pinfunction "IO137_192") (pintype "bidirectional"))
    )
    (net (code "13") (name "/2MA0") (class "Default")
      (node (ref "CON2") (pin "4") (pinfunction "4_4") (pintype "passive"))
      (node (ref "CON2") (pin "4A") (pinfunction "4_4A") (pintype "passive"))
      (node (ref "IC19") (pin "164") (pinfunction "IO13_164") (pintype "bidirectional"))
    )
    (net (code "14") (name "/2MA1") (class "Default")
      (node (ref "CON2") (pin "5") (pinfunction "5_5") (pintype "passive"))
      (node (ref "CON2") (pin "5A") (pinfunction "5_5A") (pintype "passive"))
      (node (ref "IC19") (pin "167") (pinfunction "IO16_167") (pintype "bidirectional"))
    )
    (net (code "15") (name "/2MA2") (class "Default")
      (node (ref "CON2") (pin "7") (pinfunction "7_7") (pintype "passive"))
      (node (ref "CON2") (pin "7A") (pinfunction "7_7A") (pintype "passive"))
      (node (ref "IC19") (pin "169") (pinfunction "IO67_169") (pintype "bidirectional"))
    )
    (net (code "16") (name "/2MA3") (class "Default")
      (node (ref "CON2") (pin "8") (pinfunction "8_8") (pintype "passive"))
      (node (ref "CON2") (pin "8A") (pinfunction "8_8A") (pintype "passive"))
      (node (ref "IC19") (pin "171") (pinfunction "IO70_171") (pintype "bidirectional"))
    )
    (net (code "17") (name "/2MA4") (class "Default")
      (node (ref "CON2") (pin "11") (pinfunction "11_11") (pintype "passive"))
      (node (ref "CON2") (pin "11A") (pinfunction "11_11A") (pintype "passive"))
      (node (ref "IC19") (pin "173") (pinfunction "IO73_173") (pintype "bidirectional"))
    )
    (net (code "18") (name "/2MA5") (class "Default")
      (node (ref "CON2") (pin "12") (pinfunction "12_12") (pintype "passive"))
      (node (ref "CON2") (pin "12A") (pinfunction "12_12A") (pintype "passive"))
      (node (ref "IC19") (pin "177") (pinfunction "IO78_177") (pintype "bidirectional"))
    )
    (net (code "19") (name "/2MA6") (class "Default")
      (node (ref "CON2") (pin "14") (pinfunction "14_14") (pintype "passive"))
      (node (ref "CON2") (pin "14A") (pinfunction "14_14A") (pintype "passive"))
      (node (ref "IC19") (pin "3") (pinfunction "IO195_3") (pintype "bidirectional"))
    )
    (net (code "20") (name "/2MA7") (class "Default")
      (node (ref "CON2") (pin "15") (pinfunction "15_15") (pintype "passive"))
      (node (ref "CON2") (pin "15A") (pinfunction "15_15A") (pintype "passive"))
      (node (ref "IC19") (pin "187") (pinfunction "IO144_187") (pintype "bidirectional"))
    )
    (net (code "21") (name "/2MA8") (class "Default")
      (node (ref "CON2") (pin "17") (pinfunction "17_17") (pintype "passive"))
      (node (ref "CON2") (pin "17A") (pinfunction "17_17A") (pintype "passive"))
      (node (ref "IC19") (pin "190") (pinfunction "IO139_190") (pintype "bidirectional"))
    )
    (net (code "22") (name "/2MA9") (class "Default")
      (node (ref "CON2") (pin "18") (pinfunction "18_18") (pintype "passive"))
      (node (ref "CON2") (pin "18A") (pinfunction "18_18A") (pintype "passive"))
      (node (ref "IC19") (pin "193") (pinfunction "IO136_193") (pintype "bidirectional"))
    )
    (net (code "23") (name "/15D1") (class "Default")
      (node (ref "DD1") (pin "15") (pinfunction "CO_15") (pintype "bidirectional"))
      (node (ref "DD2") (pin "15") (pinfunction "CO_15") (pintype "bidirectional"))
      (node (ref "DD3") (pin "15") (pinfunction "CO_15") (pintype "bidirectional"))
      (node (ref "DD4") (pin "15") (pinfunction "CO_15") (pintype "bidirectional"))
      (node (ref "DD8") (pin "15") (pinfunction "CO_15") (pintype "bidirectional"))
      (node (ref "DD9") (pin "15") (pinfunction "CO_15") (pintype "bidirectional"))
      (node (ref "IC19") (pin "16") (pinfunction "IO209_16") (pintype "bidirectional"))
    )
    (net (code "24") (name "/50HZ") (class "Default")
      (node (ref "IC2") (pin "2") (pinfunction "EVENT_2") (pintype "bidirectional"))
      (node (ref "S1") (pin "7") (pinfunction "2_7") (pintype "passive"))
    )
    (net (code "25") (name "/4608M") (class "Default")
      (node (ref "IC2") (pin "1") (pinfunction "CLC_1") (pintype "bidirectional"))
      (node (ref "IC4") (pin "10") (pinfunction "O_10") (pintype "open_collector"))
      (node (ref "Q2") (pin "2") (pinfunction "2_2") (pintype "passive"))
      (node (ref "R57") (pin "2") (pinfunction "2_2") (pintype "passive"))
    )
    (net (code "26") (name "/ACLO") (class "Default")
      (node (ref "DD6") (pin "10") (pinfunction "B2_10") (pintype "bidirectional"))
      (node (ref "IC1") (pin "46") (pinfunction "/ACLO_46") (pintype "bidirectional"))
      (node (ref "IC19") (pin "113") (pinfunction "IO41_113") (pintype "bidirectional"))
      (node (ref "RN6") (pin "10") (pinfunction "10_10") (pintype "passive"))
    )
    (net (code "27") (name "/ACLO_P") (class "Default")
      (node (ref "IC17") (pin "2") (pinfunction "O_2") (pintype "output"))
      (node (ref "IC19") (pin "122") (pinfunction "IO102_122") (pintype "bidirectional"))
      (node (ref "R5") (pin "1") (pinfunction "1_1") (pintype "passive"))
    )
    (net (code "28") (name "/AD0") (class "Default")
      (node (ref "CON1") (pin "3") (pinfunction "3_3") (pintype "passive"))
      (node (ref "CON2") (pin "3") (pinfunction "3_3") (pintype "passive"))
      (node (ref "DD1") (pin "10") (pinfunction "B2_10") (pintype "bidirectional"))
      (node (ref "IC1") (pin "10") (pinfunction "AD0_10") (pintype "bidirectional"))
      (node (ref "IC15") (pin "19") (pinfunction "1Q_19") (pintype "tri_state"))
      (node (ref "IC15") (pin "2") (pinfunction "1D_2") (pintype "input"))
      (node (ref "IC16") (pin "56") (pinfunction "AD0_56") (pintype "bidirectional"))
      (node (ref "IC19") (pin "73") (pinfunction "IO187_73") (pintype "bidirectional"))
      (node (ref "IC2") (pin "9") (pinfunction "AD0_9") (pintype "bidirectional"))
      (node (ref "IC3") (pin "16") (pinfunction "AD0_16") (pintype "bidirectional"))
      (node (ref "IC5") (pin "11") (pinfunction "I/O0_11") (pintype "bidirectional"))
      (node (ref "RN19") (pin "7") (pinfunction "7_7") (pintype "passive"))
    )
    (net (code "29") (name "/AD1") (class "Default")
      (node (ref "CON1") (pin "3A") (pinfunction "3_3A") (pintype "passive"))
      (node (ref "CON2") (pin "3A") (pinfunction "3_3A") (pintype "passive"))
      (node (ref "DD1") (pin "13") (pinfunction "B3_13") (pintype "bidirectional"))
      (node (ref "IC1") (pin "11") (pinfunction "AD1_11") (pintype "bidirectional"))
      (node (ref "IC15") (pin "18") (pinfunction "2Q_18") (pintype "tri_state"))
      (node (ref "IC15") (pin "3") (pinfunction "2D_3") (pintype "input"))
      (node (ref "IC16") (pin "57") (pinfunction "AD1_57") (pintype "bidirectional"))
      (node (ref "IC19") (pin "71") (pinfunction "IO185_71") (pintype "bidirectional"))
      (node (ref "IC2") (pin "10") (pinfunction "AD1_10") (pintype "bidirectional"))
      (node (ref "IC3") (pin "15") (pinfunction "AD1_15") (pintype "bidirectional"))
      (node (ref "IC5") (pin "12") (pinfunction "I/O1_12") (pintype "bidirectional"))
      (node (ref "RN19") (pin "8") (pinfunction "8_8") (pintype "passive"))
    )
    (net (code "30") (name "/AD2") (class "Default")
      (node (ref "CON1") (pin "6") (pinfunction "6_6") (pintype "passive"))
      (node (ref "CON2") (pin "6") (pinfunction "6_6") (pintype "passive"))
      (node (ref "DD1") (pin "3") (pinfunction "B0_3") (pintype "bidirectional"))
      (node (ref "IC1") (pin "12") (pinfunction "AD2_12") (pintype "bidirectional"))
      (node (ref "IC15") (pin "17") (pinfunction "3Q_17") (pintype "tri_state"))
      (node (ref "IC15") (pin "4") (pinfunction "3D_4") (pintype "input"))
      (node (ref "IC16") (pin "58") (pinfunction "AD2_58") (pintype "bidirectional"))
      (node (ref "IC19") (pin "70") (pinfunction "IO184_70") (pintype "bidirectional"))
      (node (ref "IC2") (pin "11") (pinfunction "AD2_11") (pintype "bidirectional"))
      (node (ref "IC3") (pin "14") (pinfunction "AD2_14") (pintype "bidirectional"))
      (node (ref "IC5") (pin "13") (pinfunction "I/O2_13") (pintype "bidirectional"))
      (node (ref "RN19") (pin "9") (pinfunction "9_9") (pintype "passive"))
    )
    (net (code "31") (name "/AD3") (class "Default")
      (node (ref "CON1") (pin "6A") (pinfunction "6_6A") (pintype "passive"))
      (node (ref "CON2") (pin "6A") (pinfunction "6_6A") (pintype "passive"))
      (node (ref "DD1") (pin "6") (pinfunction "B1_6") (pintype "bidirectional"))
      (node (ref "IC1") (pin "13") (pinfunction "AD3_13") (pintype "bidirectional"))
      (node (ref "IC15") (pin "16") (pinfunction "4Q_16") (pintype "tri_state"))
      (node (ref "IC15") (pin "5") (pinfunction "4D_5") (pintype "input"))
      (node (ref "IC16") (pin "59") (pinfunction "AD3_59") (pintype "bidirectional"))
      (node (ref "IC19") (pin "69") (pinfunction "IO182_69") (pintype "bidirectional"))
      (node (ref "IC2") (pin "12") (pinfunction "AD3_12") (pintype "bidirectional"))
      (node (ref "IC3") (pin "13") (pinfunction "AD3_13") (pintype "bidirectional"))
      (node (ref "IC5") (pin "15") (pinfunction "I/O3_15") (pintype "bidirectional"))
      (node (ref "RN19") (pin "10") (pinfunction "10_10") (pintype "passive"))
    )
    (net (code "32") (name "/AD4") (class "Default")
      (node (ref "CON1") (pin "10") (pinfunction "10_10") (pintype "passive"))
      (node (ref "CON2") (pin "10") (pinfunction "10_10") (pintype "passive"))
      (node (ref "DD2") (pin "10") (pinfunction "B2_10") (pintype "bidirectional"))
      (node (ref "IC1") (pin "14") (pinfunction "AD4_14") (pintype "bidirectional"))
      (node (ref "IC15") (pin "15") (pinfunction "5Q_15") (pintype "tri_state"))
      (node (ref "IC15") (pin "6") (pinfunction "5D_6") (pintype "input"))
      (node (ref "IC16") (pin "60") (pinfunction "AD4_60") (pintype "bidirectional"))
      (node (ref "IC19") (pin "68") (pinfunction "IO181_68") (pintype "bidirectional"))
      (node (ref "IC2") (pin "13") (pinfunction "AD4_13") (pintype "bidirectional"))
      (node (ref "IC3") (pin "4") (pinfunction "AD4_4") (pintype "bidirectional"))
      (node (ref "IC5") (pin "16") (pinfunction "I/O4_16") (pintype "bidirectional"))
      (node (ref "RN18") (pin "10") (pinfunction "10_10") (pintype "passive"))
    )
    (net (code "33") (name "/AD5") (class "Default")
      (node (ref "CON1") (pin "10A") (pinfunction "10_10A") (pintype "passive"))
      (node (ref "CON2") (pin "10A") (pinfunction "10_10A") (pintype "passive"))
      (node (ref "DD2") (pin "13") (pinfunction "B3_13") (pintype "bidirectional"))
      (node (ref "IC1") (pin "15") (pinfunction "AD5_15") (pintype "bidirectional"))
      (node (ref "IC15") (pin "14") (pinfunction "6Q_14") (pintype "tri_state"))
      (node (ref "IC15") (pin "7") (pinfunction "6D_7") (pintype "input"))
      (node (ref "IC16") (pin "61") (pinfunction "AD5_61") (pintype "bidirectional"))
      (node (ref "IC19") (pin "67") (pinfunction "IO179_67") (pintype "bidirectional"))
      (node (ref "IC2") (pin "14") (pinfunction "AD5_14") (pintype "bidirectional"))
      (node (ref "IC3") (pin "5") (pinfunction "AD5_5") (pintype "bidirectional"))
      (node (ref "IC5") (pin "17") (pinfunction "I/O5_17") (pintype "bidirectional"))
      (node (ref "RN18") (pin "9") (pinfunction "9_9") (pintype "passive"))
    )
    (net (code "34") (name "/AD6") (class "Default")
      (node (ref "CON1") (pin "13") (pinfunction "13_13") (pintype "passive"))
      (node (ref "CON2") (pin "13") (pinfunction "13_13") (pintype "passive"))
      (node (ref "DD2") (pin "3") (pinfunction "B0_3") (pintype "bidirectional"))
      (node (ref "IC1") (pin "16") (pinfunction "AD6_16") (pintype "bidirectional"))
      (node (ref "IC15") (pin "13") (pinfunction "7Q_13") (pintype "tri_state"))
      (node (ref "IC15") (pin "8") (pinfunction "7D_8") (pintype "input"))
      (node (ref "IC16") (pin "62") (pinfunction "AD6_62") (pintype "bidirectional"))
      (node (ref "IC19") (pin "66") (pinfunction "IO177_66") (pintype "bidirectional"))
      (node (ref "IC2") (pin "15") (pinfunction "AD6_15") (pintype "bidirectional"))
      (node (ref "IC3") (pin "6") (pinfunction "AD6_6") (pintype "bidirectional"))
      (node (ref "IC5") (pin "18") (pinfunction "I/O6_18") (pintype "bidirectional"))
      (node (ref "RN18") (pin "8") (pinfunction "8_8") (pintype "passive"))
    )
    (net (code "35") (name "/AD7") (class "Default")
      (node (ref "CON1") (pin "13A") (pinfunction "13_13A") (pintype "passive"))
      (node (ref "CON2") (pin "13A") (pinfunction "13_13A") (pintype "passive"))
      (node (ref "DD2") (pin "6") (pinfunction "B1_6") (pintype "bidirectional"))
      (node (ref "IC1") (pin "17") (pinfunction "AD7_17") (pintype "bidirectional"))
      (node (ref "IC15") (pin "12") (pinfunction "8Q_12") (pintype "tri_state"))
      (node (ref "IC15") (pin "9") (pinfunction "8D_9") (pintype "input"))
      (node (ref "IC16") (pin "64") (pinfunction "AD7_64") (pintype "bidirectional"))
      (node (ref "IC19") (pin "65") (pinfunction "IO241_65") (pintype "bidirectional"))
      (node (ref "IC2") (pin "16") (pinfunction "AD7_16") (pintype "bidirectional"))
      (node (ref "IC3") (pin "7") (pinfunction "AD7_7") (pintype "bidirectional"))
      (node (ref "IC5") (pin "19") (pinfunction "I/O7_19") (pintype "bidirectional"))
      (node (ref "RN18") (pin "7") (pinfunction "7_7") (pintype "passive"))
    )
    (net (code "36") (name "/AD8") (class "Default")
      (node (ref "CON1") (pin "16") (pinfunction "16_16") (pintype "passive"))
      (node (ref "CON2") (pin "16") (pinfunction "16_16") (pintype "passive"))
      (node (ref "DD3") (pin "10") (pinfunction "B2_10") (pintype "bidirectional"))
      (node (ref "IC1") (pin "18") (pinfunction "AD8_18") (pintype "bidirectional"))
      (node (ref "IC14") (pin "19") (pinfunction "1Q_19") (pintype "tri_state"))
      (node (ref "IC14") (pin "2") (pinfunction "1D_2") (pintype "input"))
      (node (ref "IC16") (pin "1") (pinfunction "AD8_1") (pintype "bidirectional"))
      (node (ref "IC19") (pin "64") (pinfunction "IO243_64") (pintype "bidirectional"))
      (node (ref "IC2") (pin "17") (pinfunction "AD8_17") (pintype "bidirectional"))
      (node (ref "IC3") (pin "8") (pinfunction "AD8_8") (pintype "bidirectional"))
      (node (ref "IC6") (pin "11") (pinfunction "I/O0_11") (pintype "bidirectional"))
      (node (ref "RN18") (pin "6") (pinfunction "6_6") (pintype "passive"))
    )
    (net (code "37") (name "/AD9") (class "Default")
      (node (ref "CON1") (pin "16A") (pinfunction "16_16A") (pintype "passive"))
      (node (ref "CON2") (pin "16A") (pinfunction "16_16A") (pintype "passive"))
      (node (ref "DD3") (pin "13") (pinfunction "B3_13") (pintype "bidirectional"))
      (node (ref "IC1") (pin "19") (pinfunction "AD9_19") (pintype "bidirectional"))
      (node (ref "IC14") (pin "18") (pinfunction "2Q_18") (pintype "tri_state"))
      (node (ref "IC14") (pin "3") (pinfunction "2D_3") (pintype "input"))
      (node (ref "IC16") (pin "2") (pinfunction "AD9_2") (pintype "bidirectional"))
      (node (ref "IC19") (pin "62") (pinfunction "IO245_62") (pintype "bidirectional"))
      (node (ref "IC2") (pin "18") (pinfunction "AD9_18") (pintype "bidirectional"))
      (node (ref "IC3") (pin "9") (pinfunction "AD9_9") (pintype "bidirectional"))
      (node (ref "IC6") (pin "12") (pinfunction "I/O1_12") (pintype "bidirectional"))
      (node (ref "RN18") (pin "5") (pinfunction "5_5") (pintype "passive"))
    )
    (net (code "38") (name "/AD10") (class "Default")
      (node (ref "CON1") (pin "20") (pinfunction "20_20") (pintype "passive"))
      (node (ref "CON2") (pin "20") (pinfunction "20_20") (pintype "passive"))
      (node (ref "DD3") (pin "3") (pinfunction "B0_3") (pintype "bidirectional"))
      (node (ref "IC1") (pin "20") (pinfunction "AD10_20") (pintype "bidirectional"))
      (node (ref "IC14") (pin "17") (pinfunction "3Q_17") (pintype "tri_state"))
      (node (ref "IC14") (pin "4") (pinfunction "3D_4") (pintype "input"))
      (node (ref "IC16") (pin "3") (pinfunction "AD10_3") (pintype "bidirectional"))
      (node (ref "IC19") (pin "61") (pinfunction "IO246_61") (pintype "bidirectional"))
      (node (ref "IC2") (pin "19") (pinfunction "AD10_19") (pintype "bidirectional"))
      (node (ref "IC3") (pin "10") (pinfunction "AD10_10") (pintype "bidirectional"))
      (node (ref "IC6") (pin "13") (pinfunction "I/O2_13") (pintype "bidirectional"))
      (node (ref "RN18") (pin "4") (pinfunction "4_4") (pintype "passive"))
    )
    (net (code "39") (name "/AD11") (class "Default")
      (node (ref "CON1") (pin "20A") (pinfunction "20_20A") (pintype "passive"))
      (node (ref "CON2") (pin "20A") (pinfunction "20_20A") (pintype "passive"))
      (node (ref "DD3") (pin "6") (pinfunction "B1_6") (pintype "bidirectional"))
      (node (ref "IC1") (pin "21") (pinfunction "AD11_21") (pintype "bidirectional"))
      (node (ref "IC14") (pin "16") (pinfunction "4Q_16") (pintype "tri_state"))
      (node (ref "IC14") (pin "5") (pinfunction "4D_5") (pintype "input"))
      (node (ref "IC16") (pin "4") (pinfunction "AD11_4") (pintype "bidirectional"))
      (node (ref "IC19") (pin "60") (pinfunction "IO248_60") (pintype "bidirectional"))
      (node (ref "IC2") (pin "20") (pinfunction "AD11_20") (pintype "bidirectional"))
      (node (ref "IC3") (pin "11") (pinfunction "AD11_11") (pintype "bidirectional"))
      (node (ref "IC6") (pin "15") (pinfunction "I/O3_15") (pintype "bidirectional"))
      (node (ref "RN18") (pin "3") (pinfunction "3_3") (pintype "passive"))
    )
    (net (code "40") (name "/AD12") (class "Default")
      (node (ref "CON1") (pin "23") (pinfunction "23_23") (pintype "passive"))
      (node (ref "CON2") (pin "23") (pinfunction "23_23") (pintype "passive"))
      (node (ref "DD4") (pin "10") (pinfunction "B2_10") (pintype "bidirectional"))
      (node (ref "IC1") (pin "22") (pinfunction "AD12_22") (pintype "bidirectional"))
      (node (ref "IC14") (pin "15") (pinfunction "5Q_15") (pintype "tri_state"))
      (node (ref "IC14") (pin "6") (pinfunction "5D_6") (pintype "input"))
      (node (ref "IC16") (pin "5") (pinfunction "AD12_5") (pintype "bidirectional"))
      (node (ref "IC19") (pin "59") (pinfunction "IO249_59") (pintype "bidirectional"))
      (node (ref "IC2") (pin "22") (pinfunction "AD12_22") (pintype "bidirectional"))
      (node (ref "IC3") (pin "17") (pinfunction "AD12_17") (pintype "bidirectional"))
      (node (ref "IC6") (pin "16") (pinfunction "I/O4_16") (pintype "bidirectional"))
      (node (ref "RN18") (pin "2") (pinfunction "2_2") (pintype "passive"))
    )
    (net (code "41") (name "/AD13") (class "Default")
      (node (ref "CON1") (pin "23A") (pinfunction "23_23A") (pintype "passive"))
      (node (ref "CON2") (pin "23A") (pinfunction "23_23A") (pintype "passive"))
      (node (ref "DD4") (pin "13") (pinfunction "B3_13") (pintype "bidirectional"))
      (node (ref "IC1") (pin "23") (pinfunction "AD13_23") (pintype "bidirectional"))
      (node (ref "IC14") (pin "14") (pinfunction "6Q_14") (pintype "tri_state"))
      (node (ref "IC14") (pin "7") (pinfunction "6D_7") (pintype "input"))
      (node (ref "IC16") (pin "6") (pinfunction "AD13_6") (pintype "bidirectional"))
      (node (ref "IC19") (pin "58") (pinfunction "IO251_58") (pintype "bidirectional"))
      (node (ref "IC3") (pin "18") (pinfunction "AD13_18") (pintype "bidirectional"))
      (node (ref "IC6") (pin "17") (pinfunction "I/O5_17") (pintype "bidirectional"))
      (node (ref "RN17") (pin "2") (pinfunction "2_2") (pintype "passive"))
    )
    (net (code "42") (name "/AD14") (class "Default")
      (node (ref "CON1") (pin "25") (pinfunction "25_25") (pintype "passive"))
      (node (ref "CON2") (pin "25") (pinfunction "25_25") (pintype "passive"))
      (node (ref "DD4") (pin "3") (pinfunction "B0_3") (pintype "bidirectional"))
      (node (ref "IC1") (pin "24") (pinfunction "AD14_24") (pintype "bidirectional"))
      (node (ref "IC14") (pin "13") (pinfunction "7Q_13") (pintype "tri_state"))
      (node (ref "IC14") (pin "8") (pinfunction "7D_8") (pintype "input"))
      (node (ref "IC16") (pin "7") (pinfunction "AD14_7") (pintype "bidirectional"))
      (node (ref "IC19") (pin "57") (pinfunction "IO253_57") (pintype "bidirectional"))
      (node (ref "IC3") (pin "19") (pinfunction "AD14_19") (pintype "bidirectional"))
      (node (ref "IC6") (pin "18") (pinfunction "I/O6_18") (pintype "bidirectional"))
      (node (ref "RN17") (pin "3") (pinfunction "3_3") (pintype "passive"))
    )
    (net (code "43") (name "/AD15") (class "Default")
      (node (ref "CON1") (pin "25A") (pinfunction "25_25A") (pintype "passive"))
      (node (ref "CON2") (pin "25A") (pinfunction "25_25A") (pintype "passive"))
      (node (ref "DD4") (pin "6") (pinfunction "B1_6") (pintype "bidirectional"))
      (node (ref "IC1") (pin "25") (pinfunction "AD15_25") (pintype "bidirectional"))
      (node (ref "IC14") (pin "12") (pinfunction "8Q_12") (pintype "tri_state"))
      (node (ref "IC14") (pin "9") (pinfunction "8D_9") (pintype "input"))
      (node (ref "IC16") (pin "8") (pinfunction "AD15_8") (pintype "bidirectional"))
      (node (ref "IC19") (pin "56") (pinfunction "IO254_56") (pintype "bidirectional"))
      (node (ref "IC2") (pin "25") (pinfunction "AD15_25") (pintype "bidirectional"))
      (node (ref "IC3") (pin "20") (pinfunction "AD15_20") (pintype "bidirectional"))
      (node (ref "IC6") (pin "19") (pinfunction "I/O7_19") (pintype "bidirectional"))
      (node (ref "RN17") (pin "4") (pinfunction "4_4") (pintype "passive"))
    )
    (net (code "44") (name "/AD16") (class "Default")
      (node (ref "DD8") (pin "10") (pinfunction "B2_10") (pintype "bidirectional"))
      (node (ref "IC1") (pin "26") (pinfunction "AD16_26") (pintype "bidirectional"))
      (node (ref "IC19") (pin "55") (pinfunction "IO256_55") (pintype "bidirectional"))
      (node (ref "RN17") (pin "5") (pinfunction "5_5") (pintype "passive"))
    )
    (net (code "45") (name "/AD17") (class "Default")
      (node (ref "DD8") (pin "13") (pinfunction "B3_13") (pintype "bidirectional"))
      (node (ref "IC1") (pin "27") (pinfunction "AD17_27") (pintype "bidirectional"))
      (node (ref "IC19") (pin "49") (pinfunction "IO225_49") (pintype "bidirectional"))
      (node (ref "RN17") (pin "6") (pinfunction "6_6") (pintype "passive"))
    )
    (net (code "46") (name "/AD18") (class "Default")
      (node (ref "DD8") (pin "3") (pinfunction "B0_3") (pintype "bidirectional"))
      (node (ref "IC1") (pin "28") (pinfunction "AD18_28") (pintype "bidirectional"))
      (node (ref "IC19") (pin "48") (pinfunction "IO227_48") (pintype "bidirectional"))
      (node (ref "RN17") (pin "7") (pinfunction "7_7") (pintype "passive"))
    )
    (net (code "47") (name "/AD19") (class "Default")
      (node (ref "DD8") (pin "6") (pinfunction "B1_6") (pintype "bidirectional"))
      (node (ref "IC1") (pin "29") (pinfunction "AD19_29") (pintype "bidirectional"))
      (node (ref "IC19") (pin "47") (pinfunction "IO229_47") (pintype "bidirectional"))
      (node (ref "RN17") (pin "8") (pinfunction "8_8") (pintype "passive"))
    )
    (net (code "48") (name "/AD20") (class "Default")
      (node (ref "DD9") (pin "3") (pinfunction "B0_3") (pintype "bidirectional"))
      (node (ref "IC1") (pin "30") (pinfunction "AD20_30") (pintype "bidirectional"))
      (node (ref "IC19") (pin "46") (pinfunction "IO230_46") (pintype "bidirectional"))
      (node (ref "RN17") (pin "9") (pinfunction "9_9") (pintype "passive"))
    )
    (net (code "49") (name "/AD21") (class "Default")
      (node (ref "DD9") (pin "6") (pinfunction "B1_6") (pintype "bidirectional"))
      (node (ref "IC1") (pin "31") (pinfunction "AD21_31") (pintype "bidirectional"))
      (node (ref "IC19") (pin "45") (pinfunction "IO232_45") (pintype "bidirectional"))
      (node (ref "RN17") (pin "10") (pinfunction "10_10") (pintype "passive"))
    )
    (net (code "50") (name "/BAD0") (class "Default")
      (node (ref "DD1") (pin "11") (pinfunction "O2_11") (pintype "bidirectional"))
      (node (ref "DD1") (pin "9") (pinfunction "I2_9") (pintype "bidirectional"))
      (node (ref "RN8") (pin "2") (pinfunction "1_2") (pintype "passive"))
      (node (ref "XP1") (pin "AB17") (pinfunction "/BDAL0_AB17") (pintype "bidirectional"))
    )
    (net (code "51") (name "/BAD1") (class "Default")
      (node (ref "DD1") (pin "12") (pinfunction "I3_12") (pintype "bidirectional"))
      (node (ref "DD1") (pin "14") (pinfunction "O3_14") (pintype "bidirectional"))
      (node (ref "RN8") (pin "3") (pinfunction "1_3") (pintype "passive"))
      (node (ref "XP1") (pin "AB18") (pinfunction "/BDAL1_AB18") (pintype "bidirectional"))
    )
    (net (code "52") (name "/BAD2") (class "Default")
      (node (ref "DD1") (pin "2") (pinfunction "O0_2") (pintype "bidirectional"))
      (node (ref "DD1") (pin "4") (pinfunction "I0_4") (pintype "bidirectional"))
      (node (ref "RN8") (pin "4") (pinfunction "1_4") (pintype "passive"))
      (node (ref "XP1") (pin "BB5") (pinfunction "/BDAL2_BB5") (pintype "bidirectional"))
    )
    (net (code "53") (name "/BAD3") (class "Default")
      (node (ref "DD1") (pin "5") (pinfunction "O1_5") (pintype "bidirectional"))
      (node (ref "DD1") (pin "7") (pinfunction "I1_7") (pintype "bidirectional"))
      (node (ref "RN8") (pin "5") (pinfunction "1_5") (pintype "passive"))
      (node (ref "XP1") (pin "BB6") (pinfunction "/BDAL3_BB6") (pintype "bidirectional"))
    )
    (net (code "54") (name "/BAD4") (class "Default")
      (node (ref "DD2") (pin "11") (pinfunction "O2_11") (pintype "bidirectional"))
      (node (ref "DD2") (pin "9") (pinfunction "I2_9") (pintype "bidirectional"))
      (node (ref "RN5") (pin "2") (pinfunction "1_2") (pintype "passive"))
      (node (ref "XP1") (pin "BB7") (pinfunction "/BDAL4_BB7") (pintype "bidirectional"))
    )
    (net (code "55") (name "/BAD5") (class "Default")
      (node (ref "DD2") (pin "12") (pinfunction "I3_12") (pintype "bidirectional"))
      (node (ref "DD2") (pin "14") (pinfunction "O3_14") (pintype "bidirectional"))
      (node (ref "RN5") (pin "3") (pinfunction "1_3") (pintype "passive"))
      (node (ref "XP1") (pin "BB8") (pinfunction "/BDAL5_BB8") (pintype "bidirectional"))
    )
    (net (code "56") (name "/BAD6") (class "Default")
      (node (ref "DD2") (pin "2") (pinfunction "O0_2") (pintype "bidirectional"))
      (node (ref "DD2") (pin "4") (pinfunction "I0_4") (pintype "bidirectional"))
      (node (ref "RN5") (pin "4") (pinfunction "1_4") (pintype "passive"))
      (node (ref "XP1") (pin "BB9") (pinfunction "/BDAL6_BB9") (pintype "bidirectional"))
    )
    (net (code "57") (name "/BAD7") (class "Default")
      (node (ref "DD2") (pin "5") (pinfunction "O1_5") (pintype "bidirectional"))
      (node (ref "DD2") (pin "7") (pinfunction "I1_7") (pintype "bidirectional"))
      (node (ref "RN5") (pin "5") (pinfunction "1_5") (pintype "passive"))
      (node (ref "XP1") (pin "BB10") (pinfunction "/BDAL7_BB10") (pintype "bidirectional"))
    )
    (net (code "58") (name "/BAD8") (class "Default")
      (node (ref "DD3") (pin "11") (pinfunction "O2_11") (pintype "bidirectional"))
      (node (ref "DD3") (pin "9") (pinfunction "I2_9") (pintype "bidirectional"))
      (node (ref "RN4") (pin "2") (pinfunction "1_2") (pintype "passive"))
      (node (ref "XP1") (pin "BB11") (pinfunction "/BDAL8_BB11") (pintype "bidirectional"))
    )
    (net (code "59") (name "/BAD9") (class "Default")
      (node (ref "DD3") (pin "12") (pinfunction "I3_12") (pintype "bidirectional"))
      (node (ref "DD3") (pin "14") (pinfunction "O3_14") (pintype "bidirectional"))
      (node (ref "RN4") (pin "3") (pinfunction "1_3") (pintype "passive"))
      (node (ref "XP1") (pin "BB12") (pinfunction "/BDAL9_BB12") (pintype "bidirectional"))
    )
    (net (code "60") (name "/BAD10") (class "Default")
      (node (ref "DD3") (pin "2") (pinfunction "O0_2") (pintype "bidirectional"))
      (node (ref "DD3") (pin "4") (pinfunction "I0_4") (pintype "bidirectional"))
      (node (ref "RN4") (pin "4") (pinfunction "1_4") (pintype "passive"))
      (node (ref "XP1") (pin "BB13") (pinfunction "/BDAL10_BB13") (pintype "bidirectional"))
    )
    (net (code "61") (name "/BAD11") (class "Default")
      (node (ref "DD3") (pin "5") (pinfunction "O1_5") (pintype "bidirectional"))
      (node (ref "DD3") (pin "7") (pinfunction "I1_7") (pintype "bidirectional"))
      (node (ref "RN4") (pin "5") (pinfunction "1_5") (pintype "passive"))
      (node (ref "XP1") (pin "BB14") (pinfunction "/BDAL11_BB14") (pintype "bidirectional"))
    )
    (net (code "62") (name "/BAD12") (class "Default")
      (node (ref "DD4") (pin "11") (pinfunction "O2_11") (pintype "bidirectional"))
      (node (ref "DD4") (pin "9") (pinfunction "I2_9") (pintype "bidirectional"))
      (node (ref "RN7") (pin "2") (pinfunction "1_2") (pintype "passive"))
      (node (ref "XP1") (pin "BB15") (pinfunction "/BDAL12_BB15") (pintype "bidirectional"))
    )
    (net (code "63") (name "/BAD13") (class "Default")
      (node (ref "DD4") (pin "12") (pinfunction "I3_12") (pintype "bidirectional"))
      (node (ref "DD4") (pin "14") (pinfunction "O3_14") (pintype "bidirectional"))
      (node (ref "RN7") (pin "3") (pinfunction "1_3") (pintype "passive"))
      (node (ref "XP1") (pin "BB16") (pinfunction "/BDAL13_BB16") (pintype "bidirectional"))
    )
    (net (code "64") (name "/BAD14") (class "Default")
      (node (ref "DD4") (pin "2") (pinfunction "O0_2") (pintype "bidirectional"))
      (node (ref "DD4") (pin "4") (pinfunction "I0_4") (pintype "bidirectional"))
      (node (ref "RN7") (pin "4") (pinfunction "1_4") (pintype "passive"))
      (node (ref "XP1") (pin "BB17") (pinfunction "/BDAL14_BB17") (pintype "bidirectional"))
    )
    (net (code "65") (name "/BAD15") (class "Default")
      (node (ref "DD4") (pin "5") (pinfunction "O1_5") (pintype "bidirectional"))
      (node (ref "DD4") (pin "7") (pinfunction "I1_7") (pintype "bidirectional"))
      (node (ref "RN7") (pin "5") (pinfunction "1_5") (pintype "passive"))
      (node (ref "XP1") (pin "BB18") (pinfunction "/BDAL15_BB18") (pintype "bidirectional"))
    )
    (net (code "66") (name "/BAD16") (class "Default")
      (node (ref "DD8") (pin "11") (pinfunction "O2_11") (pintype "bidirectional"))
      (node (ref "DD8") (pin "9") (pinfunction "I2_9") (pintype "bidirectional"))
      (node (ref "RN9") (pin "2") (pinfunction "1_2") (pintype "passive"))
      (node (ref "XP1") (pin "AA3") (pinfunction "/BDAL16_AA3") (pintype "bidirectional"))
    )
    (net (code "67") (name "/BAD17") (class "Default")
      (node (ref "DD8") (pin "12") (pinfunction "I3_12") (pintype "bidirectional"))
      (node (ref "DD8") (pin "14") (pinfunction "O3_14") (pintype "bidirectional"))
      (node (ref "RN9") (pin "3") (pinfunction "1_3") (pintype "passive"))
      (node (ref "XP1") (pin "AA4") (pinfunction "/BDAL17_AA4") (pintype "bidirectional"))
    )
    (net (code "68") (name "/BAD18") (class "Default")
      (node (ref "DD8") (pin "2") (pinfunction "O0_2") (pintype "bidirectional"))
      (node (ref "DD8") (pin "4") (pinfunction "I0_4") (pintype "bidirectional"))
      (node (ref "RN9") (pin "4") (pinfunction "1_4") (pintype "passive"))
      (node (ref "XP1") (pin "BA3") (pinfunction "/BDAL18_BA3") (pintype "bidirectional"))
    )
    (net (code "69") (name "/BAD19") (class "Default")
      (node (ref "DD8") (pin "5") (pinfunction "O1_5") (pintype "bidirectional"))
      (node (ref "DD8") (pin "7") (pinfunction "I1_7") (pintype "bidirectional"))
      (node (ref "RN9") (pin "5") (pinfunction "1_5") (pintype "passive"))
      (node (ref "XP1") (pin "BA4") (pinfunction "/BDAL19_BA4") (pintype "bidirectional"))
    )
    (net (code "70") (name "/BAD20") (class "Default")
      (node (ref "DD9") (pin "2") (pinfunction "O0_2") (pintype "bidirectional"))
      (node (ref "DD9") (pin "4") (pinfunction "I0_4") (pintype "bidirectional"))
      (node (ref "RN10") (pin "2") (pinfunction "1_2") (pintype "passive"))
      (node (ref "XP1") (pin "BA5") (pinfunction "/BDAL20_BA5") (pintype "bidirectional"))
    )
    (net (code "71") (name "/BAD21") (class "Default")
      (node (ref "DD9") (pin "5") (pinfunction "O1_5") (pintype "bidirectional"))
      (node (ref "DD9") (pin "7") (pinfunction "I1_7") (pintype "bidirectional"))
      (node (ref "RN10") (pin "3") (pinfunction "1_3") (pintype "passive"))
      (node (ref "XP1") (pin "BA6") (pinfunction "/BDAL21_BA6") (pintype "bidirectional"))
    )
    (net (code "72") (name "/BBS7") (class "Default")
      (node (ref "DD16") (pin "3") (pinfunction "B0_3") (pintype "bidirectional"))
      (node (ref "RN15") (pin "3") (pinfunction "1_3") (pintype "passive"))
      (node (ref "XP1") (pin "AB13") (pinfunction "/BBS7_AB13") (pintype "bidirectional"))
    )
    (net (code "73") (name "/BDCOK") (class "Default")
      (node (ref "DD6") (pin "7") (pinfunction "I1_7") (pintype "bidirectional"))
      (node (ref "RN16") (pin "3") (pinfunction "1_3") (pintype "passive"))
      (node (ref "XP1") (pin "BA1") (pinfunction "BDCOK_BA1") (pintype "bidirectional"))
    )
    (net (code "74") (name "/BDIN") (class "Default")
      (node (ref "DD15") (pin "6") (pinfunction "B1_6") (pintype "bidirectional"))
      (node (ref "RN14") (pin "3") (pinfunction "1_3") (pintype "passive"))
      (node (ref "XP1") (pin "AB7") (pinfunction "/BDIN_AB7") (pintype "bidirectional"))
    )
    (net (code "75") (name "/BDMGO") (class "Default")
      (node (ref "DD14") (pin "5") (pinfunction "O1_5") (pintype "bidirectional"))
      (node (ref "RN13") (pin "3") (pinfunction "1_3") (pintype "passive"))
      (node (ref "XP1") (pin "AB15") (pinfunction "/BDMGO_AB15") (pintype "bidirectional"))
    )
    (net (code "76") (name "/BDMR") (class "Default")
      (node (ref "DD5") (pin "7") (pinfunction "I1_7") (pintype "bidirectional"))
      (node (ref "RN11") (pin "2") (pinfunction "1_2") (pintype "passive"))
      (node (ref "XP1") (pin "AA12") (pinfunction "/BDMR_AA12") (pintype "bidirectional"))
    )
    (net (code "77") (name "/BDOUT") (class "Default")
      (node (ref "DD15") (pin "10") (pinfunction "B2_10") (pintype "bidirectional"))
      (node (ref "RN14") (pin "4") (pinfunction "1_4") (pintype "passive"))
      (node (ref "XP1") (pin "AB5") (pinfunction "/BDOUT_AB5") (pintype "bidirectional"))
    )
    (net (code "78") (name "/BEVNT") (class "Default")
      (node (ref "DD5") (pin "12") (pinfunction "I3_12") (pintype "bidirectional"))
      (node (ref "RN11") (pin "4") (pinfunction "1_4") (pintype "passive"))
      (node (ref "XP1") (pin "BA14") (pinfunction "/BEVNT_BA14") (pintype "bidirectional"))
    )
    (net (code "79") (name "/BHALT") (class "Default")
      (node (ref "DD6") (pin "4") (pinfunction "I0_4") (pintype "bidirectional"))
      (node (ref "RN16") (pin "2") (pinfunction "1_2") (pintype "passive"))
      (node (ref "XP1") (pin "AA13") (pinfunction "/BHALT_AA13") (pintype "bidirectional"))
    )
    (net (code "80") (name "/BHLTM") (class "Default")
      (node (ref "DD14") (pin "2") (pinfunction "O0_2") (pintype "bidirectional"))
      (node (ref "RN13") (pin "2") (pinfunction "1_2") (pintype "passive"))
      (node (ref "XP1") (pin "BA7") (pinfunction "P$7_BA7") (pintype "bidirectional"))
    )
    (net (code "81") (name "/BIAKO") (class "Default")
      (node (ref "DD14") (pin "11") (pinfunction "O2_11") (pintype "bidirectional"))
      (node (ref "RN13") (pin "4") (pinfunction "1_4") (pintype "passive"))
      (node (ref "XP1") (pin "AB12") (pinfunction "/BIAKO_AB12") (pintype "bidirectional"))
    )
    (net (code "82") (name "/BINIT") (class "Default")
      (node (ref "DD14") (pin "14") (pinfunction "O3_14") (pintype "bidirectional"))
      (node (ref "RN13") (pin "5") (pinfunction "1_5") (pintype "passive"))
      (node (ref "XP1") (pin "AB16") (pinfunction "/BINIT_AB16") (pintype "bidirectional"))
    )
    (net (code "83") (name "/BIRQ4") (class "Default")
      (node (ref "DD7") (pin "12") (pinfunction "I3_12") (pintype "bidirectional"))
      (node (ref "RN12") (pin "5") (pinfunction "1_5") (pintype "passive"))
      (node (ref "XP1") (pin "AB10") (pinfunction "/BIRQ4_AB10") (pintype "bidirectional"))
    )
    (net (code "84") (name "/BIRQ5") (class "Default")
      (node (ref "DD7") (pin "9") (pinfunction "I2_9") (pintype "bidirectional"))
      (node (ref "RN12") (pin "4") (pinfunction "1_4") (pintype "passive"))
      (node (ref "XP1") (pin "AA1") (pinfunction "/BIRQ5_AA1") (pintype "bidirectional"))
    )
    (net (code "85") (name "/BIRQ6") (class "Default")
      (node (ref "DD7") (pin "7") (pinfunction "I1_7") (pintype "bidirectional"))
      (node (ref "RN12") (pin "3") (pinfunction "1_3") (pintype "passive"))
      (node (ref "XP1") (pin "AA2") (pinfunction "/BIRQ6_AA2") (pintype "bidirectional"))
    )
    (net (code "86") (name "/BIRQ7") (class "Default")
      (node (ref "DD7") (pin "4") (pinfunction "I0_4") (pintype "bidirectional"))
      (node (ref "RN12") (pin "2") (pinfunction "1_2") (pintype "passive"))
      (node (ref "XP1") (pin "BA13") (pinfunction "/BIRQ7_BA13") (pintype "bidirectional"))
    )
    (net (code "87") (name "/BPOK") (class "Default")
      (node (ref "DD6") (pin "12") (pinfunction "I3_12") (pintype "bidirectional"))
      (node (ref "DD6") (pin "9") (pinfunction "I2_9") (pintype "bidirectional"))
      (node (ref "RN16") (pin "4") (pinfunction "1_4") (pintype "passive"))
      (node (ref "XP1") (pin "BA2") (pinfunction "BPOK_BA2") (pintype "bidirectional"))
    )
    (net (code "88") (name "/BRPLY") (class "Default")
      (node (ref "DD16") (pin "11") (pinfunction "O2_11") (pintype "bidirectional"))
      (node (ref "DD16") (pin "9") (pinfunction "I2_9") (pintype "bidirectional"))
      (node (ref "RN15") (pin "5") (pinfunction "1_5") (pintype "passive"))
      (node (ref "XP1") (pin "AB6") (pinfunction "/BRPLY_AB6") (pintype "bidirectional"))
    )
    (net (code "89") (name "/BS") (class "Default")
      (node (ref "IC1") (pin "34") (pinfunction "/BS_34") (pintype "bidirectional"))
      (node (ref "IC19") (pin "114") (pinfunction "IO43_114") (pintype "bidirectional"))
      (node (ref "RN1") (pin "3") (pinfunction "3_3") (pintype "passive"))
    )
    (net (code "90") (name "/BS7") (class "Default")
      (node (ref "DD16") (pin "2") (pinfunction "O0_2") (pintype "bidirectional"))
      (node (ref "DD16") (pin "4") (pinfunction "I0_4") (pintype "bidirectional"))
      (node (ref "IC19") (pin "44") (pinfunction "IO233_44") (pintype "bidirectional"))
      (node (ref "IC2") (pin "26") (pinfunction "BS_26") (pintype "bidirectional"))
      (node (ref "RN20") (pin "2") (pinfunction "2_2") (pintype "passive"))
    )
    (net (code "91") (name "/BSACK") (class "Default")
      (node (ref "DD5") (pin "9") (pinfunction "I2_9") (pintype "bidirectional"))
      (node (ref "RN11") (pin "3") (pinfunction "1_3") (pintype "passive"))
      (node (ref "XP1") (pin "BA12") (pinfunction "/BSACK_BA12") (pintype "bidirectional"))
    )
    (net (code "92") (name "/BSYNC") (class "Default")
      (node (ref "DD15") (pin "3") (pinfunction "B0_3") (pintype "bidirectional"))
      (node (ref "RN14") (pin "2") (pinfunction "1_2") (pintype "passive"))
      (node (ref "XP1") (pin "AB8") (pinfunction "/BSYNC_AB8") (pintype "bidirectional"))
    )
    (net (code "93") (name "/BWTBT") (class "Default")
      (node (ref "DD15") (pin "13") (pinfunction "B3_13") (pintype "bidirectional"))
      (node (ref "RN14") (pin "5") (pinfunction "1_5") (pintype "passive"))
      (node (ref "XP1") (pin "AB9") (pinfunction "/BWTBT_AB9") (pintype "bidirectional"))
    )
    (net (code "94") (name "/CAS0") (class "Default")
      (node (ref "CON1") (pin "2") (pinfunction "2_2") (pintype "passive"))
      (node (ref "IC19") (pin "159") (pinfunction "IO5_159") (pintype "bidirectional"))
    )
    (net (code "95") (name "/CAS1") (class "Default")
      (node (ref "CON1") (pin "2A") (pinfunction "2_2A") (pintype "passive"))
      (node (ref "IC19") (pin "160") (pinfunction "IO6_160") (pintype "bidirectional"))
    )
    (net (code "96") (name "/CAS2") (class "Default")
      (node (ref "CON2") (pin "2") (pinfunction "2_2") (pintype "passive"))
      (node (ref "IC19") (pin "161") (pinfunction "IO8_161") (pintype "bidirectional"))
    )
    (net (code "97") (name "/CAS3") (class "Default")
      (node (ref "CON2") (pin "2A") (pinfunction "2_2A") (pintype "passive"))
      (node (ref "IC19") (pin "162") (pinfunction "IO9_162") (pintype "bidirectional"))
    )
    (net (code "98") (name "/CB0") (class "Default")
      (node (ref "IC15") (pin "11") (pinfunction "CLK_11") (pintype "input"))
      (node (ref "IC19") (pin "136") (pinfunction "IO89_136") (pintype "bidirectional"))
    )
    (net (code "99") (name "/CB1") (class "Default")
      (node (ref "IC14") (pin "11") (pinfunction "CLK_11") (pintype "input"))
      (node (ref "IC19") (pin "135") (pinfunction "IO88_135") (pintype "bidirectional"))
    )
    (net (code "100") (name "/CE0_ROM") (class "Default")
      (node (ref "IC19") (pin "133") (pinfunction "IO86_133") (pintype "bidirectional"))
    )
    (net (code "101") (name "/CE1_ROM") (class "Default")
      (node (ref "IC19") (pin "131") (pinfunction "IO83_131") (pintype "bidirectional"))
    )
    (net (code "102") (name "/CLK") (class "Default")
      (node (ref "IC1") (pin "60") (pinfunction "/CLK_60") (pintype "bidirectional"))
      (node (ref "IC16") (pin "24") (pinfunction "CLK_24") (pintype "bidirectional"))
      (node (ref "IC19") (pin "96") (pinfunction "IO54_96") (pintype "bidirectional"))
    )
    (net (code "103") (name "/CS0_PULT") (class "Default")
      (node (ref "IC19") (pin "100") (pinfunction "IO61_100") (pintype "bidirectional"))
      (node (ref "IC5") (pin "20") (pinfunction "~{CS}_20") (pintype "input"))
    )
    (net (code "104") (name "/CS1_PULT") (class "Default")
      (node (ref "IC19") (pin "102") (pinfunction "IO64_102") (pintype "bidirectional"))
      (node (ref "IC6") (pin "20") (pinfunction "~{CS}_20") (pintype "input"))
    )
    (net (code "105") (name "/CS_ROM") (class "Default")
      (node (ref "IC19") (pin "99") (pinfunction "IO59_99") (pintype "bidirectional"))
      (node (ref "IC3") (pin "23") (pinfunction "CE_23") (pintype "bidirectional"))
    )
    (net (code "106") (name "/DCLO") (class "Default")
      (node (ref "DD6") (pin "6") (pinfunction "B1_6") (pintype "bidirectional"))
      (node (ref "IC1") (pin "52") (pinfunction "/DCLO_52") (pintype "bidirectional"))
      (node (ref "IC16") (pin "13") (pinfunction "/DCLO_13") (pintype "bidirectional"))
      (node (ref "IC19") (pin "117") (pinfunction "IO46_117") (pintype "bidirectional"))
      (node (ref "IC2") (pin "40") (pinfunction "DCLO_40") (pintype "bidirectional"))
      (node (ref "RN6") (pin "9") (pinfunction "9_9") (pintype "passive"))
    )
    (net (code "107") (name "/DCLO_P") (class "Default")
      (node (ref "IC17") (pin "10") (pinfunction "O_10") (pintype "output"))
      (node (ref "IC19") (pin "123") (pinfunction "IO104_123") (pintype "bidirectional"))
      (node (ref "R3") (pin "1") (pinfunction "1_1") (pintype "passive"))
      (node (ref "R4") (pin "2") (pinfunction "2_2") (pintype "passive"))
    )
    (net (code "108") (name "/DIN") (class "Default")
      (node (ref "DD15") (pin "5") (pinfunction "O1_5") (pintype "bidirectional"))
      (node (ref "DD15") (pin "7") (pinfunction "I1_7") (pintype "bidirectional"))
      (node (ref "IC19") (pin "34") (pinfunction "IO168_34") (pintype "bidirectional"))
      (node (ref "IC2") (pin "38") (pinfunction "DIN_38") (pintype "bidirectional"))
      (node (ref "IC3") (pin "1") (pinfunction "DIN_1") (pintype "bidirectional"))
      (node (ref "RN20") (pin "3") (pinfunction "3_3") (pintype "passive"))
    )
    (net (code "109") (name "/DIN_VM") (class "Default")
      (node (ref "IC1") (pin "1") (pinfunction "/DIN_1") (pintype "bidirectional"))
      (node (ref "IC16") (pin "18") (pinfunction "/DIN_18") (pintype "bidirectional"))
      (node (ref "IC19") (pin "92") (pinfunction "IO49_92") (pintype "bidirectional"))
      (node (ref "RN6") (pin "2") (pinfunction "2_2") (pintype "passive"))
    )
    (net (code "110") (name "/DMGO") (class "Default")
      (node (ref "DD14") (pin "6") (pinfunction "B1_6") (pintype "bidirectional"))
      (node (ref "IC1") (pin "6") (pinfunction "/DMGO_6") (pintype "bidirectional"))
      (node (ref "RN19") (pin "4") (pinfunction "4_4") (pintype "passive"))
    )
    (net (code "111") (name "/DMR") (class "Default")
      (node (ref "DD5") (pin "6") (pinfunction "B1_6") (pintype "bidirectional"))
      (node (ref "IC1") (pin "8") (pinfunction "/DMR_8") (pintype "bidirectional"))
      (node (ref "RN19") (pin "6") (pinfunction "6_6") (pintype "passive"))
    )
    (net (code "112") (name "/DOUT") (class "Default")
      (node (ref "DD15") (pin "11") (pinfunction "O2_11") (pintype "bidirectional"))
      (node (ref "DD15") (pin "9") (pinfunction "I2_9") (pintype "bidirectional"))
      (node (ref "IC19") (pin "33") (pinfunction "IO169_33") (pintype "bidirectional"))
      (node (ref "IC2") (pin "37") (pinfunction "DOUT_37") (pintype "bidirectional"))
      (node (ref "RN20") (pin "4") (pinfunction "4_4") (pintype "passive"))
    )
    (net (code "113") (name "/DOUT_VM") (class "Default")
      (node (ref "IC1") (pin "2") (pinfunction "/DOUT_2") (pintype "bidirectional"))
      (node (ref "IC16") (pin "20") (pinfunction "DOUT_20") (pintype "bidirectional"))
      (node (ref "IC19") (pin "93") (pinfunction "IO51_93") (pintype "bidirectional"))
      (node (ref "IC5") (pin "27") (pinfunction "~{WE}_27") (pintype "input"))
      (node (ref "IC6") (pin "27") (pinfunction "~{WE}_27") (pintype "input"))
      (node (ref "RN6") (pin "3") (pinfunction "3_3") (pintype "passive"))
    )
    (net (code "114") (name "/ESYNC") (class "Default")
      (node (ref "IC19") (pin "26") (pinfunction "IO147_26") (pintype "bidirectional"))
      (node (ref "IC2") (pin "41") (pinfunction "SYNC_41") (pintype "bidirectional"))
    )
    (net (code "115") (name "/EVNT") (class "Default")
      (node (ref "DD5") (pin "13") (pinfunction "B3_13") (pintype "bidirectional"))
      (node (ref "IC1") (pin "44") (pinfunction "/EVNT_44") (pintype "bidirectional"))
      (node (ref "IC19") (pin "89") (pinfunction "IO125_89") (pintype "bidirectional"))
      (node (ref "RN1") (pin "10") (pinfunction "10_10") (pintype "passive"))
      (node (ref "S1") (pin "2") (pinfunction "1_2") (pintype "passive"))
    )
    (net (code "116") (name "/EX_SYNC") (class "Default")
      (node (ref "DD15") (pin "2") (pinfunction "O0_2") (pintype "bidirectional"))
      (node (ref "IC19") (pin "28") (pinfunction "IO176_28") (pintype "bidirectional"))
      (node (ref "RN20") (pin "8") (pinfunction "8_8") (pintype "passive"))
    )
    (net (code "117") (name "/HLT") (class "Default")
      (node (ref "DD6") (pin "3") (pinfunction "B0_3") (pintype "bidirectional"))
      (node (ref "IC1") (pin "47") (pinfunction "/HLT_47") (pintype "bidirectional"))
      (node (ref "IC19") (pin "84") (pinfunction "IO118_84") (pintype "bidirectional"))
      (node (ref "RN3") (pin "7") (pinfunction "7_7") (pintype "passive"))
      (node (ref "S1") (pin "8") (pinfunction "2_8") (pintype "passive"))
    )
    (net (code "118") (name "/HLTM") (class "Default")
      (node (ref "D3") (pin "K") (pinfunction "C_K") (pintype "passive"))
      (node (ref "DD14") (pin "3") (pinfunction "B0_3") (pintype "bidirectional"))
      (node (ref "IC1") (pin "55") (pinfunction "/HLTM_55") (pintype "bidirectional"))
      (node (ref "IC19") (pin "43") (pinfunction "IO235_43") (pintype "bidirectional"))
      (node (ref "RN2") (pin "9") (pinfunction "9_9") (pintype "passive"))
    )
    (net (code "119") (name "/HLT_KEY") (class "Default")
      (node (ref "DD6") (pin "13") (pinfunction "B3_13") (pintype "bidirectional"))
      (node (ref "S1") (pin "1") (pinfunction "1_1") (pintype "passive"))
    )
    (net (code "120") (name "/HLT_P") (class "Default")
      (node (ref "IC17") (pin "4") (pinfunction "O_4") (pintype "output"))
      (node (ref "IC19") (pin "129") (pinfunction "IO112_129") (pintype "bidirectional"))
    )
    (net (code "121") (name "/IAKO") (class "Default")
      (node (ref "DD14") (pin "10") (pinfunction "B2_10") (pintype "bidirectional"))
      (node (ref "IC19") (pin "37") (pinfunction "IO163_37") (pintype "bidirectional"))
      (node (ref "IC2") (pin "36") (pinfunction "IAKO_36") (pintype "bidirectional"))
    )
    (net (code "122") (name "/IAK_VM") (class "Default")
      (node (ref "IC1") (pin "62") (pinfunction "/IAKO_62") (pintype "bidirectional"))
      (node (ref "IC2") (pin "33") (pinfunction "IAKI_33") (pintype "bidirectional"))
      (node (ref "RN2") (pin "3") (pinfunction "3_3") (pintype "passive"))
    )
    (net (code "123") (name "/INIT") (class "Default")
      (node (ref "DD14") (pin "13") (pinfunction "B3_13") (pintype "bidirectional"))
      (node (ref "IC1") (pin "33") (pinfunction "/INIT_33") (pintype "bidirectional"))
      (node (ref "IC19") (pin "86") (pinfunction "IO120_86") (pintype "bidirectional"))
      (node (ref "IC2") (pin "34") (pinfunction "INIT_34") (pintype "bidirectional"))
      (node (ref "RN1") (pin "2") (pinfunction "2_2") (pintype "passive"))
    )
    (net (code "124") (name "/INIT_P") (class "Default")
      (node (ref "IC17") (pin "6") (pinfunction "O_6") (pintype "output"))
      (node (ref "IC19") (pin "128") (pinfunction "IO110_128") (pintype "bidirectional"))
    )
    (net (code "125") (name "/IRQ0") (class "Default")
      (node (ref "DD7") (pin "13") (pinfunction "B3_13") (pintype "bidirectional"))
      (node (ref "IC1") (pin "51") (pinfunction "/IRQ0_51") (pintype "bidirectional"))
      (node (ref "IC2") (pin "35") (pinfunction "VIRQ_35") (pintype "bidirectional"))
      (node (ref "RN3") (pin "3") (pinfunction "3_3") (pintype "passive"))
    )
    (net (code "126") (name "/IRQ1") (class "Default")
      (node (ref "DD7") (pin "10") (pinfunction "B2_10") (pintype "bidirectional"))
      (node (ref "IC1") (pin "50") (pinfunction "/IRQ1_50") (pintype "bidirectional"))
      (node (ref "RN3") (pin "4") (pinfunction "4_4") (pintype "passive"))
    )
    (net (code "127") (name "/IRQ2") (class "Default")
      (node (ref "DD7") (pin "6") (pinfunction "B1_6") (pintype "bidirectional"))
      (node (ref "IC1") (pin "49") (pinfunction "/IRQ2_49") (pintype "bidirectional"))
      (node (ref "RN3") (pin "5") (pinfunction "5_5") (pintype "passive"))
    )
    (net (code "128") (name "/IRQ3") (class "Default")
      (node (ref "DD7") (pin "3") (pinfunction "B0_3") (pintype "bidirectional"))
      (node (ref "IC1") (pin "48") (pinfunction "/IRQ3_48") (pintype "bidirectional"))
      (node (ref "RN3") (pin "6") (pinfunction "6_6") (pintype "passive"))
    )
    (net (code "129") (name "/LA") (class "Default")
      (node (ref "DD15") (pin "4") (pinfunction "I0_4") (pintype "bidirectional"))
      (node (ref "IC19") (pin "40") (pinfunction "IO238_40") (pintype "bidirectional"))
    )
    (net (code "130") (name "/MCLK") (class "Default")
      (node (ref "IC19") (pin "184") (pinfunction "GCLK1_184") (pintype "input"))
      (node (ref "IC4") (pin "4") (pinfunction "O_4") (pintype "open_collector"))
      (node (ref "Q1") (pin "2") (pinfunction "2_2") (pintype "passive"))
      (node (ref "R45") (pin "2") (pinfunction "2_2") (pintype "passive"))
    )
    (net (code "131") (name "/OE_RAM") (class "Default")
      (node (ref "IC19") (pin "130") (pinfunction "IO81_130") (pintype "bidirectional"))
      (node (ref "IC5") (pin "22") (pinfunction "~{OE}_22") (pintype "input"))
      (node (ref "IC6") (pin "22") (pinfunction "~{OE}_22") (pintype "input"))
    )
    (net (code "132") (name "/OE_ROM") (class "Default")
      (node (ref "IC19") (pin "132") (pinfunction "IO85_132") (pintype "bidirectional"))
    )
    (net (code "133") (name "/PA0") (class "Default")
      (node (ref "IC19") (pin "154") (pinfunction "IO3_154") (pintype "bidirectional"))
      (node (ref "IC5") (pin "10") (pinfunction "A0_10") (pintype "input"))
      (node (ref "IC6") (pin "10") (pinfunction "A0_10") (pintype "input"))
    )
    (net (code "134") (name "/PA1") (class "Default")
      (node (ref "IC19") (pin "153") (pinfunction "IO1_153") (pintype "bidirectional"))
      (node (ref "IC5") (pin "9") (pinfunction "A1_9") (pintype "input"))
      (node (ref "IC6") (pin "9") (pinfunction "A1_9") (pintype "input"))
    )
    (net (code "135") (name "/PA2") (class "Default")
      (node (ref "IC19") (pin "151") (pinfunction "IO32_151") (pintype "bidirectional"))
      (node (ref "IC5") (pin "8") (pinfunction "A2_8") (pintype "input"))
      (node (ref "IC6") (pin "8") (pinfunction "A2_8") (pintype "input"))
    )
    (net (code "136") (name "/PA3") (class "Default")
      (node (ref "IC19") (pin "150") (pinfunction "IO30_150") (pintype "bidirectional"))
      (node (ref "IC5") (pin "7") (pinfunction "A3_7") (pintype "input"))
      (node (ref "IC6") (pin "7") (pinfunction "A3_7") (pintype "input"))
    )
    (net (code "137") (name "/PA4") (class "Default")
      (node (ref "IC19") (pin "149") (pinfunction "IO29_149") (pintype "bidirectional"))
      (node (ref "IC5") (pin "6") (pinfunction "A4_6") (pintype "input"))
      (node (ref "IC6") (pin "6") (pinfunction "A4_6") (pintype "input"))
    )
    (net (code "138") (name "/PA5") (class "Default")
      (node (ref "IC19") (pin "148") (pinfunction "IO27_148") (pintype "bidirectional"))
      (node (ref "IC5") (pin "5") (pinfunction "A5_5") (pintype "input"))
      (node (ref "IC6") (pin "5") (pinfunction "A5_5") (pintype "input"))
    )
    (net (code "139") (name "/PA6") (class "Default")
      (node (ref "IC19") (pin "147") (pinfunction "IO25_147") (pintype "bidirectional"))
      (node (ref "IC5") (pin "4") (pinfunction "A6_4") (pintype "input"))
      (node (ref "IC6") (pin "4") (pinfunction "A6_4") (pintype "input"))
    )
    (net (code "140") (name "/PA7") (class "Default")
      (node (ref "IC19") (pin "146") (pinfunction "IO24_146") (pintype "bidirectional"))
      (node (ref "IC5") (pin "3") (pinfunction "A7_3") (pintype "input"))
      (node (ref "IC6") (pin "3") (pinfunction "A7_3") (pintype "input"))
    )
    (net (code "141") (name "/PA8") (class "Default")
      (node (ref "IC19") (pin "145") (pinfunction "IO22_145") (pintype "bidirectional"))
      (node (ref "IC5") (pin "25") (pinfunction "A8_25") (pintype "input"))
      (node (ref "IC6") (pin "25") (pinfunction "A8_25") (pintype "input"))
    )
    (net (code "142") (name "/PA9") (class "Default")
      (node (ref "IC19") (pin "144") (pinfunction "IO21_144") (pintype "bidirectional"))
      (node (ref "IC5") (pin "24") (pinfunction "A9_24") (pintype "input"))
      (node (ref "IC6") (pin "24") (pinfunction "A9_24") (pintype "input"))
    )
    (net (code "143") (name "/PA10") (class "Default")
      (node (ref "IC19") (pin "142") (pinfunction "IO19_142") (pintype "bidirectional"))
      (node (ref "IC5") (pin "21") (pinfunction "A10_21") (pintype "input"))
      (node (ref "IC6") (pin "21") (pinfunction "A10_21") (pintype "input"))
    )
    (net (code "144") (name "/PA11") (class "Default")
      (node (ref "IC19") (pin "141") (pinfunction "IO17_141") (pintype "bidirectional"))
      (node (ref "IC5") (pin "23") (pinfunction "A11_23") (pintype "input"))
      (node (ref "IC6") (pin "23") (pinfunction "A11_23") (pintype "input"))
    )
    (net (code "145") (name "/PA12") (class "Default")
      (node (ref "IC19") (pin "140") (pinfunction "IO96_140") (pintype "bidirectional"))
      (node (ref "IC5") (pin "2") (pinfunction "A12_2") (pintype "input"))
      (node (ref "IC6") (pin "2") (pinfunction "A12_2") (pintype "input"))
    )
    (net (code "146") (name "/PA13") (class "Default")
      (node (ref "IC19") (pin "139") (pinfunction "IO94_139") (pintype "bidirectional"))
      (node (ref "IC5") (pin "26") (pinfunction "A13_26") (pintype "input"))
      (node (ref "IC6") (pin "26") (pinfunction "A13_26") (pintype "input"))
    )
    (net (code "147") (name "/PA14") (class "Default")
      (node (ref "IC19") (pin "138") (pinfunction "IO93_138") (pintype "bidirectional"))
      (node (ref "IC5") (pin "1") (pinfunction "A14_1") (pintype "input"))
      (node (ref "IC6") (pin "1") (pinfunction "A14_1") (pintype "input"))
    )
    (net (code "148") (name "/P_UART") (class "Default")
      (node (ref "IC2") (pin "23") (pinfunction "ACL0_23") (pintype "bidirectional"))
      (node (ref "R58") (pin "2") (pinfunction "2_2") (pintype "passive"))
      (node (ref "S1") (pin "6") (pinfunction "2_6") (pintype "passive"))
    )
    (net (code "149") (name "/RAS0") (class "Default")
      (node (ref "CON1") (pin "27") (pinfunction "27_27") (pintype "passive"))
      (node (ref "IC19") (pin "196") (pinfunction "IO131_196") (pintype "bidirectional"))
    )
    (net (code "150") (name "/RAS1") (class "Default")
      (node (ref "CON2") (pin "27") (pinfunction "27_27") (pintype "passive"))
      (node (ref "IC19") (pin "197") (pinfunction "IO129_197") (pintype "bidirectional"))
    )
    (net (code "151") (name "/RAS2") (class "Default")
      (node (ref "CON1") (pin "27A") (pinfunction "27_27A") (pintype "passive"))
      (node (ref "IC19") (pin "198") (pinfunction "IO208_198") (pintype "bidirectional"))
    )
    (net (code "152") (name "/RAS3") (class "Default")
      (node (ref "CON2") (pin "27A") (pinfunction "27_27A") (pintype "passive"))
      (node (ref "IC19") (pin "199") (pinfunction "IO206_199") (pintype "bidirectional"))
    )
    (net (code "153") (name "/RB") (class "Default")
      (node (ref "IC14") (pin "1") (pinfunction "OC_1") (pintype "input"))
      (node (ref "IC15") (pin "1") (pinfunction "OC_1") (pintype "input"))
      (node (ref "IC19") (pin "137") (pinfunction "IO91_137") (pintype "bidirectional"))
    )
    (net (code "154") (name "/RCLK") (class "Default")
      (node (ref "C10") (pin "1") (pinfunction "1_1") (pintype "passive"))
      (node (ref "IC19") (pin "24") (pinfunction "IO150_24") (pintype "bidirectional"))
      (node (ref "IC4") (pin "8") (pinfunction "O_8") (pintype "open_collector"))
    )
    (net (code "155") (name "/RESET") (class "Default")
      (node (ref "IC17") (pin "11") (pinfunction "I_11") (pintype "input"))
      (node (ref "IC17") (pin "12") (pinfunction "O_12") (pintype "output"))
      (node (ref "IC19") (pin "182") (pinfunction "GCLR/_182") (pintype "input"))
    )
    (net (code "156") (name "/RPLY") (class "Default")
      (node (ref "IC19") (pin "81") (pinfunction "IO117_81") (pintype "bidirectional"))
      (node (ref "IC2") (pin "39") (pinfunction "RPLY_39") (pintype "bidirectional"))
      (node (ref "IC3") (pin "2") (pinfunction "RPLY_2") (pintype "bidirectional"))
      (node (ref "RN20") (pin "5") (pinfunction "5_5") (pintype "passive"))
    )
    (net (code "157") (name "/RPLY_VM") (class "Default")
      (node (ref "DD16") (pin "10") (pinfunction "B2_10") (pintype "bidirectional"))
      (node (ref "IC1") (pin "5") (pinfunction "/RPLY_5") (pintype "bidirectional"))
      (node (ref "IC16") (pin "19") (pinfunction "RPLY_19") (pintype "bidirectional"))
      (node (ref "IC19") (pin "91") (pinfunction "IO128_91") (pintype "bidirectional"))
      (node (ref "RN19") (pin "3") (pinfunction "3_3") (pintype "passive"))
    )
    (net (code "158") (name "/RX") (class "Default")
      (node (ref "IC19") (pin "108") (pinfunction "IO33_108") (pintype "bidirectional"))
      (node (ref "IC39") (pin "12") (pinfunction "R1OUT_12") (pintype "output"))
    )
    (net (code "159") (name "/SACK") (class "Default")
      (node (ref "DD15") (pin "15") (pinfunction "CO_15") (pintype "bidirectional"))
      (node (ref "DD16") (pin "15") (pinfunction "CO_15") (pintype "bidirectional"))
      (node (ref "DD5") (pin "10") (pinfunction "B2_10") (pintype "bidirectional"))
      (node (ref "IC1") (pin "7") (pinfunction "/SACK_7") (pintype "bidirectional"))
      (node (ref "IC16") (pin "21") (pinfunction "/SACK_21") (pintype "bidirectional"))
      (node (ref "IC19") (pin "36") (pinfunction "IO165_36") (pintype "bidirectional"))
      (node (ref "RN19") (pin "5") (pinfunction "5_5") (pintype "passive"))
    )
    (net (code "160") (name "/SACK_B") (class "Default")
      (node (ref "DD15") (pin "1") (pinfunction "CI_1") (pintype "bidirectional"))
      (node (ref "DD16") (pin "1") (pinfunction "CI_1") (pintype "bidirectional"))
      (node (ref "IC19") (pin "38") (pinfunction "IO161_38") (pintype "bidirectional"))
    )
    (net (code "161") (name "/SEL") (class "Default")
      (node (ref "DD16") (pin "5") (pinfunction "O1_5") (pintype "bidirectional"))
      (node (ref "DD16") (pin "7") (pinfunction "I1_7") (pintype "bidirectional"))
      (node (ref "IC1") (pin "35") (pinfunction "/SEL_35") (pintype "bidirectional"))
      (node (ref "IC19") (pin "115") (pinfunction "IO45_115") (pintype "bidirectional"))
      (node (ref "RN1") (pin "4") (pinfunction "4_4") (pintype "passive"))
    )
    (net (code "162") (name "/SSPARE_SEL") (class "Default")
      (node (ref "DD16") (pin "6") (pinfunction "B1_6") (pintype "bidirectional"))
      (node (ref "RN15") (pin "4") (pinfunction "1_4") (pintype "passive"))
      (node (ref "XP1") (pin "AA7") (pinfunction "P$7_AA7") (pintype "bidirectional"))
    )
    (net (code "163") (name "/SSYNC") (class "Default")
      (node (ref "IC1") (pin "4") (pinfunction "/SSYNC_4") (pintype "bidirectional"))
      (node (ref "IC16") (pin "23") (pinfunction "/SSYNC_23") (pintype "bidirectional"))
      (node (ref "IC19") (pin "35") (pinfunction "IO166_35") (pintype "bidirectional"))
      (node (ref "RN19") (pin "2") (pinfunction "2_2") (pintype "passive"))
    )
    (net (code "164") (name "/SYNC") (class "Default")
      (node (ref "IC1") (pin "3") (pinfunction "/SYNC_3") (pintype "bidirectional"))
      (node (ref "IC16") (pin "22") (pinfunction "/SYNC_22") (pintype "bidirectional"))
      (node (ref "IC19") (pin "42") (pinfunction "IO237_42") (pintype "bidirectional"))
      (node (ref "IC3") (pin "3") (pinfunction "SYNC_3") (pintype "bidirectional"))
      (node (ref "RN6") (pin "4") (pinfunction "4_4") (pintype "passive"))
    )
    (net (code "165") (name "/TA") (class "Default")
      (node (ref "IC1") (pin "36") (pinfunction "/TA_36") (pintype "bidirectional"))
      (node (ref "IC19") (pin "121") (pinfunction "IO101_121") (pintype "bidirectional"))
      (node (ref "RN1") (pin "5") (pinfunction "5_5") (pintype "passive"))
    )
    (net (code "166") (name "/TCK") (class "Default")
      (node (ref "IC19") (pin "30") (pinfunction "TCK-IO173_30") (pintype "bidirectional"))
      (node (ref "JP3") (pin "1") (pinfunction "1_1") (pintype "passive"))
      (node (ref "R1") (pin "2") (pinfunction "2_2") (pintype "passive"))
    )
    (net (code "167") (name "/TDI") (class "Default")
      (node (ref "IC19") (pin "176") (pinfunction "IO77-TDI_176") (pintype "bidirectional"))
      (node (ref "JP3") (pin "9") (pinfunction "9_9") (pintype "passive"))
      (node (ref "R7") (pin "2") (pinfunction "2_2") (pintype "passive"))
    )
    (net (code "168") (name "/TDO") (class "Default")
      (node (ref "IC19") (pin "189") (pinfunction "TDO-IO141_189") (pintype "bidirectional"))
      (node (ref "JP3") (pin "3") (pinfunction "3_3") (pintype "passive"))
    )
    (net (code "169") (name "/TMS") (class "Default")
      (node (ref "IC19") (pin "127") (pinfunction "IO109-TMS_127") (pintype "bidirectional"))
      (node (ref "JP3") (pin "5") (pinfunction "5_5") (pintype "passive"))
      (node (ref "R8") (pin "2") (pinfunction "2_2") (pintype "passive"))
    )
    (net (code "170") (name "/TX") (class "Default")
      (node (ref "IC19") (pin "110") (pinfunction "IO37_110") (pintype "bidirectional"))
      (node (ref "IC39") (pin "11") (pinfunction "T1IN_11") (pintype "input"))
    )
    (net (code "171") (name "/UMAP_VM") (class "Default")
      (node (ref "IC1") (pin "37") (pinfunction "/UMAP_37") (pintype "bidirectional"))
      (node (ref "RN1") (pin "6") (pinfunction "6_6") (pintype "passive"))
    )
    (net (code "172") (name "/WE0") (class "Default")
      (node (ref "CON1") (pin "21") (pinfunction "21_21") (pintype "passive"))
      (node (ref "CON1") (pin "21A") (pinfunction "21_21A") (pintype "passive"))
      (node (ref "IC19") (pin "194") (pinfunction "IO134_194") (pintype "bidirectional"))
    )
    (net (code "173") (name "/WE1") (class "Default")
      (node (ref "CON2") (pin "21") (pinfunction "21_21") (pintype "passive"))
      (node (ref "CON2") (pin "21A") (pinfunction "21_21A") (pintype "passive"))
      (node (ref "IC19") (pin "195") (pinfunction "IO133_195") (pintype "bidirectional"))
    )
    (net (code "174") (name "/WO") (class "Default")
      (node (ref "IC1") (pin "59") (pinfunction "/WO_59") (pintype "bidirectional"))
      (node (ref "IC19") (pin "124") (pinfunction "IO105_124") (pintype "bidirectional"))
      (node (ref "RN2") (pin "5") (pinfunction "5_5") (pintype "passive"))
      (node (ref "S1") (pin "5") (pinfunction "2_5") (pintype "passive"))
    )
    (net (code "175") (name "/WTBT") (class "Default")
      (node (ref "DD15") (pin "12") (pinfunction "I3_12") (pintype "bidirectional"))
      (node (ref "DD15") (pin "14") (pinfunction "O3_14") (pintype "bidirectional"))
      (node (ref "IC19") (pin "22") (pinfunction "IO152_22") (pintype "bidirectional"))
      (node (ref "RN20") (pin "6") (pinfunction "6_6") (pintype "passive"))
    )
    (net (code "176") (name "/WTBT_VM") (class "Default")
      (node (ref "IC1") (pin "63") (pinfunction "/WTBT_63") (pintype "bidirectional"))
      (node (ref "IC19") (pin "120") (pinfunction "IO99_120") (pintype "bidirectional"))
      (node (ref "RN2") (pin "2") (pinfunction "2_2") (pintype "passive"))
    )
    (net (code "177") (name "/{slash}DREADY") (class "Default")
      (node (ref "IC1") (pin "56") (pinfunction "/DREADY_56") (pintype "bidirectional"))
      (node (ref "IC16") (pin "17") (pinfunction "/DREADY_17") (pintype "bidirectional"))
      (node (ref "RN2") (pin "8") (pinfunction "8_8") (pintype "passive"))
    )
    (net (code "178") (name "/{slash}FD") (class "Default")
      (node (ref "IC1") (pin "58") (pinfunction "/FD_58") (pintype "bidirectional"))
      (node (ref "IC16") (pin "10") (pinfunction "/FD_10") (pintype "bidirectional"))
      (node (ref "RN2") (pin "6") (pinfunction "6_6") (pintype "passive"))
    )
    (net (code "179") (name "/{slash}FL") (class "Default")
      (node (ref "IC1") (pin "57") (pinfunction "/FL_57") (pintype "bidirectional"))
      (node (ref "IC16") (pin "11") (pinfunction "/FL_11") (pintype "bidirectional"))
      (node (ref "RN2") (pin "7") (pinfunction "7_7") (pintype "passive"))
    )
    (net (code "180") (name "/{slash}FPPRD") (class "Default")
      (node (ref "IC1") (pin "54") (pinfunction "/FPPRD_54") (pintype "bidirectional"))
      (node (ref "IC16") (pin "15") (pinfunction "/FPPRD_15") (pintype "bidirectional"))
      (node (ref "RN2") (pin "10") (pinfunction "10_10") (pintype "passive"))
    )
    (net (code "181") (name "/{slash}FPPTR") (class "Default")
      (node (ref "IC1") (pin "53") (pinfunction "/FPPTRP_53") (pintype "bidirectional"))
      (node (ref "IC16") (pin "14") (pinfunction "FPPTRP_14") (pintype "bidirectional"))
      (node (ref "RN3") (pin "2") (pinfunction "2_2") (pintype "passive"))
    )
    (net (code "182") (name "/{slash}LIN") (class "Default")
      (node (ref "IC1") (pin "61") (pinfunction "/LIN_61") (pintype "bidirectional"))
      (node (ref "IC16") (pin "12") (pinfunction "/LIN_12") (pintype "bidirectional"))
      (node (ref "RN2") (pin "4") (pinfunction "4_4") (pintype "passive"))
    )
    (net (code "183") (name "/{slash}RX") (class "Default")
      (node (ref "IC19") (pin "109") (pinfunction "IO35_109") (pintype "bidirectional"))
      (node (ref "IC2") (pin "28") (pinfunction "IP_28") (pintype "bidirectional"))
    )
    (net (code "184") (name "/{slash}TX") (class "Default")
      (node (ref "IC19") (pin "111") (pinfunction "IO38_111") (pintype "bidirectional"))
      (node (ref "IC2") (pin "27") (pinfunction "TF_27") (pintype "bidirectional"))
    )
    (net (code "185") (name "GND") (class "Default")
      (node (ref "C1") (pin "-") (pinfunction "-_-") (pintype "passive"))
      (node (ref "C12") (pin "2") (pinfunction "2_2") (pintype "passive"))
      (node (ref "C13") (pin "2") (pinfunction "2_2") (pintype "passive"))
      (node (ref "C14") (pin "2") (pinfunction "2_2") (pintype "passive"))
      (node (ref "C15") (pin "2") (pinfunction "2_2") (pintype "passive"))
      (node (ref "C16") (pin "2") (pinfunction "2_2") (pintype "passive"))
      (node (ref "C17") (pin "2") (pinfunction "2_2") (pintype "passive"))
      (node (ref "C18") (pin "-") (pinfunction "-_-") (pintype "passive"))
      (node (ref "C19") (pin "-") (pinfunction "-_-") (pintype "passive"))
      (node (ref "C2") (pin "2") (pinfunction "2_2") (pintype "passive"))
      (node (ref "C20") (pin "2") (pinfunction "2_2") (pintype "passive"))
      (node (ref "C21") (pin "2") (pinfunction "2_2") (pintype "passive"))
      (node (ref "C22") (pin "2") (pinfunction "2_2") (pintype "passive"))
      (node (ref "C23") (pin "2") (pinfunction "2_2") (pintype "passive"))
      (node (ref "C24") (pin "2") (pinfunction "2_2") (pintype "passive"))
      (node (ref "C25") (pin "2") (pinfunction "2_2") (pintype "passive"))
      (node (ref "C26") (pin "2") (pinfunction "2_2") (pintype "passive"))
      (node (ref "C27") (pin "-") (pinfunction "-_-") (pintype "passive"))
      (node (ref "C28") (pin "2") (pinfunction "2_2") (pintype "passive"))
      (node (ref "C29") (pin "2") (pinfunction "2_2") (pintype "passive"))
      (node (ref "C3") (pin "-") (pinfunction "-_-") (pintype "passive"))
      (node (ref "C30") (pin "2") (pinfunction "2_2") (pintype "passive"))
      (node (ref "C36") (pin "2") (pinfunction "2_2") (pintype "passive"))
      (node (ref "C37") (pin "2") (pinfunction "2_2") (pintype "passive"))
      (node (ref "C4") (pin "-") (pinfunction "-_-") (pintype "passive"))
      (node (ref "C5") (pin "-") (pinfunction "-_-") (pintype "passive"))
      (node (ref "C6") (pin "-") (pinfunction "-_-") (pintype "passive"))
      (node (ref "C7") (pin "2") (pinfunction "2_2") (pintype "passive"))
      (node (ref "C8") (pin "2") (pinfunction "2_2") (pintype "passive"))
      (node (ref "CON1") (pin "19") (pinfunction "19_19") (pintype "passive"))
      (node (ref "CON1") (pin "19A") (pinfunction "19_19A") (pintype "passive"))
      (node (ref "CON1") (pin "22") (pinfunction "22_22") (pintype "passive"))
      (node (ref "CON1") (pin "22A") (pinfunction "22_22A") (pintype "passive"))
      (node (ref "CON1") (pin "9") (pinfunction "9_9") (pintype "passive"))
      (node (ref "CON1") (pin "9A") (pinfunction "9_9A") (pintype "passive"))
      (node (ref "CON2") (pin "19") (pinfunction "19_19") (pintype "passive"))
      (node (ref "CON2") (pin "19A") (pinfunction "19_19A") (pintype "passive"))
      (node (ref "CON2") (pin "22") (pinfunction "22_22") (pintype "passive"))
      (node (ref "CON2") (pin "22A") (pinfunction "22_22A") (pintype "passive"))
      (node (ref "CON2") (pin "9") (pinfunction "9_9") (pintype "passive"))
      (node (ref "CON2") (pin "9A") (pinfunction "9_9A") (pintype "passive"))
      (node (ref "D8") (pin "K") (pinfunction "C_K") (pintype "passive"))
      (node (ref "D9") (pin "K") (pinfunction "C_K") (pintype "passive"))
      (node (ref "DD1") (pin "8") (pinfunction "GND_8") (pintype "bidirectional"))
      (node (ref "DD14") (pin "15") (pinfunction "CO_15") (pintype "bidirectional"))
      (node (ref "DD14") (pin "8") (pinfunction "GND_8") (pintype "bidirectional"))
      (node (ref "DD15") (pin "8") (pinfunction "GND_8") (pintype "bidirectional"))
      (node (ref "DD16") (pin "8") (pinfunction "GND_8") (pintype "bidirectional"))
      (node (ref "DD2") (pin "8") (pinfunction "GND_8") (pintype "bidirectional"))
      (node (ref "DD3") (pin "8") (pinfunction "GND_8") (pintype "bidirectional"))
      (node (ref "DD4") (pin "8") (pinfunction "GND_8") (pintype "bidirectional"))
      (node (ref "DD5") (pin "1") (pinfunction "CI_1") (pintype "bidirectional"))
      (node (ref "DD5") (pin "8") (pinfunction "GND_8") (pintype "bidirectional"))
      (node (ref "DD6") (pin "1") (pinfunction "CI_1") (pintype "bidirectional"))
      (node (ref "DD6") (pin "8") (pinfunction "GND_8") (pintype "bidirectional"))
      (node (ref "DD7") (pin "1") (pinfunction "CI_1") (pintype "bidirectional"))
      (node (ref "DD7") (pin "8") (pinfunction "GND_8") (pintype "bidirectional"))
      (node (ref "DD8") (pin "8") (pinfunction "GND_8") (pintype "bidirectional"))
      (node (ref "DD9") (pin "8") (pinfunction "GND_8") (pintype "bidirectional"))
      (node (ref "IC1") (pin "32") (pinfunction "GND_32") (pintype "bidirectional"))
      (node (ref "IC1") (pin "38") (pinfunction "GND_38") (pintype "bidirectional"))
      (node (ref "IC1") (pin "40") (pinfunction "GND_40") (pintype "bidirectional"))
      (node (ref "IC1") (pin "41") (pinfunction "GND_41") (pintype "bidirectional"))
      (node (ref "IC1") (pin "42") (pinfunction "GND_42") (pintype "bidirectional"))
      (node (ref "IC1") (pin "45") (pinfunction "/ET_45") (pintype "bidirectional"))
      (node (ref "IC1") (pin "9") (pinfunction "GND_9") (pintype "bidirectional"))
      (node (ref "IC16") (pin "25") (pinfunction "GND_25") (pintype "bidirectional"))
      (node (ref "IC16") (pin "33") (pinfunction "GND_33") (pintype "bidirectional"))
      (node (ref "IC16") (pin "9") (pinfunction "GND_9") (pintype "bidirectional"))
      (node (ref "IC19") (pin "116") (pinfunction "GND_116") (pintype "power_in"))
      (node (ref "IC19") (pin "134") (pinfunction "GND_134") (pintype "power_in"))
      (node (ref "IC19") (pin "14") (pinfunction "GND_14") (pintype "power_in"))
      (node (ref "IC19") (pin "152") (pinfunction "GND_152") (pintype "power_in"))
      (node (ref "IC19") (pin "174") (pinfunction "GND_174") (pintype "power_in"))
      (node (ref "IC19") (pin "180") (pinfunction "GND_180") (pintype "power_in"))
      (node (ref "IC19") (pin "185") (pinfunction "GND_185") (pintype "power_in"))
      (node (ref "IC19") (pin "200") (pinfunction "GND_200") (pintype "power_in"))
      (node (ref "IC19") (pin "32") (pinfunction "GND_32") (pintype "power_in"))
      (node (ref "IC19") (pin "50") (pinfunction "GND_50") (pintype "power_in"))
      (node (ref "IC19") (pin "72") (pinfunction "GND_72") (pintype "power_in"))
      (node (ref "IC19") (pin "75") (pinfunction "GND_75") (pintype "power_in"))
      (node (ref "IC19") (pin "82") (pinfunction "GND_82") (pintype "power_in"))
      (node (ref "IC19") (pin "94") (pinfunction "GND_94") (pintype "power_in"))
      (node (ref "IC2") (pin "21") (pinfunction "GND_21") (pintype "bidirectional"))
      (node (ref "IC2") (pin "24") (pinfunction "ACL1_24") (pintype "bidirectional"))
      (node (ref "IC2") (pin "29") (pinfunction "BSYD_29") (pintype "bidirectional"))
      (node (ref "IC2") (pin "4") (pinfunction "FR1_4") (pintype "bidirectional"))
      (node (ref "IC2") (pin "5") (pinfunction "FR2_5") (pintype "bidirectional"))
      (node (ref "IC3") (pin "12") (pinfunction "GND_12") (pintype "bidirectional"))
      (node (ref "IC5") (pin "14") (pinfunction "VSS_14") (pintype "power_in"))
      (node (ref "IC6") (pin "14") (pinfunction "VSS_14") (pintype "power_in"))
      (node (ref "JP3") (pin "10") (pinfunction "10_10") (pintype "passive"))
      (node (ref "JP3") (pin "2") (pinfunction "2_2") (pintype "passive"))
      (node (ref "R1") (pin "1") (pinfunction "1_1") (pintype "passive"))
      (node (ref "RN10") (pin "6") (pinfunction "1_6") (pintype "passive"))
      (node (ref "RN11") (pin "6") (pinfunction "1_6") (pintype "passive"))
      (node (ref "RN12") (pin "6") (pinfunction "1_6") (pintype "passive"))
      (node (ref "RN13") (pin "6") (pinfunction "1_6") (pintype "passive"))
      (node (ref "RN14") (pin "6") (pinfunction "1_6") (pintype "passive"))
      (node (ref "RN15") (pin "6") (pinfunction "1_6") (pintype "passive"))
      (node (ref "RN16") (pin "6") (pinfunction "1_6") (pintype "passive"))
      (node (ref "RN4") (pin "6") (pinfunction "1_6") (pintype "passive"))
      (node (ref "RN5") (pin "6") (pinfunction "1_6") (pintype "passive"))
      (node (ref "RN7") (pin "6") (pinfunction "1_6") (pintype "passive"))
      (node (ref "RN8") (pin "6") (pinfunction "1_6") (pintype "passive"))
      (node (ref "RN9") (pin "6") (pinfunction "1_6") (pintype "passive"))
      (node (ref "S1") (pin "3") (pinfunction "1_3") (pintype "passive"))
      (node (ref "S1") (pin "4") (pinfunction "1_4") (pintype "passive"))
      (node (ref "S2") (pin "1") (pinfunction "1_1") (pintype "passive"))
      (node (ref "S4") (pin "1") (pinfunction "1_1") (pintype "passive"))
      (node (ref "S5") (pin "1") (pinfunction "1_1") (pintype "passive"))
      (node (ref "X2") (pin "5") (pinfunction "5_5") (pintype "passive"))
      (node (ref "X2") (pin "G2") (pinfunction "G2_G2") (pintype "passive"))
      (node (ref "XP1") (pin "AA11") (pinfunction "GND_AA11") (pintype "bidirectional"))
      (node (ref "XP1") (pin "AA16") (pinfunction "GND_AA16") (pintype "bidirectional"))
      (node (ref "XP1") (pin "AA8") (pinfunction "GND_AA8") (pintype "bidirectional"))
      (node (ref "XP1") (pin "AB3") (pinfunction "GND_AB3") (pintype "bidirectional"))
      (node (ref "XP1") (pin "BA11") (pinfunction "GND_BA11") (pintype "bidirectional"))
      (node (ref "XP1") (pin "BA16") (pinfunction "GND_BA16") (pintype "bidirectional"))
      (node (ref "XP1") (pin "BA8") (pinfunction "GND_BA8") (pintype "bidirectional"))
      (node (ref "XP1") (pin "BB3") (pinfunction "GND_BB3") (pintype "bidirectional"))
    )
    (net (code "186") (name "Net-(D3-PadA)") (class "Default")
      (node (ref "D3") (pin "A") (pinfunction "A_A") (pintype "passive"))
      (node (ref "R65") (pin "1") (pinfunction "1_1") (pintype "passive"))
    )
    (net (code "187") (name "Net-(D8-PadA)") (class "Default")
      (node (ref "D8") (pin "A") (pinfunction "A_A") (pintype "passive"))
      (node (ref "R4") (pin "1") (pinfunction "1_1") (pintype "passive"))
    )
    (net (code "188") (name "Net-(D9-PadA)") (class "Default")
      (node (ref "D9") (pin "A") (pinfunction "A_A") (pintype "passive"))
      (node (ref "R5") (pin "2") (pinfunction "2_2") (pintype "passive"))
    )
    (net (code "189") (name "Net-(IC4A-I)") (class "Default")
      (node (ref "IC4") (pin "1") (pinfunction "I_1") (pintype "input"))
      (node (ref "Q1") (pin "1") (pinfunction "1_1") (pintype "passive"))
      (node (ref "R44") (pin "1") (pinfunction "1_1") (pintype "passive"))
    )
    (net (code "190") (name "Net-(IC4A-O)") (class "Default")
      (node (ref "C9") (pin "2") (pinfunction "2_2") (pintype "passive"))
      (node (ref "IC4") (pin "2") (pinfunction "O_2") (pintype "open_collector"))
      (node (ref "R44") (pin "2") (pinfunction "2_2") (pintype "passive"))
    )
    (net (code "191") (name "Net-(IC4B-I)") (class "Default")
      (node (ref "C9") (pin "1") (pinfunction "1_1") (pintype "passive"))
      (node (ref "IC4") (pin "3") (pinfunction "I_3") (pintype "input"))
      (node (ref "R45") (pin "1") (pinfunction "1_1") (pintype "passive"))
    )
    (net (code "192") (name "Net-(IC4C-I)") (class "Default")
      (node (ref "C10") (pin "2") (pinfunction "2_2") (pintype "passive"))
      (node (ref "IC4") (pin "5") (pinfunction "I_5") (pintype "input"))
      (node (ref "R46") (pin "1") (pinfunction "1_1") (pintype "passive"))
    )
    (net (code "193") (name "Net-(IC4C-O)") (class "Default")
      (node (ref "IC4") (pin "6") (pinfunction "O_6") (pintype "open_collector"))
      (node (ref "IC4") (pin "9") (pinfunction "I_9") (pintype "input"))
      (node (ref "R46") (pin "2") (pinfunction "2_2") (pintype "passive"))
    )
    (net (code "194") (name "Net-(IC4E-I)") (class "Default")
      (node (ref "C11") (pin "1") (pinfunction "1_1") (pintype "passive"))
      (node (ref "IC4") (pin "11") (pinfunction "I_11") (pintype "input"))
      (node (ref "R57") (pin "1") (pinfunction "1_1") (pintype "passive"))
    )
    (net (code "195") (name "Net-(IC4F-I)") (class "Default")
      (node (ref "IC4") (pin "13") (pinfunction "I_13") (pintype "input"))
      (node (ref "Q2") (pin "1") (pinfunction "1_1") (pintype "passive"))
      (node (ref "R56") (pin "1") (pinfunction "1_1") (pintype "passive"))
    )
    (net (code "196") (name "Net-(IC4F-O)") (class "Default")
      (node (ref "C11") (pin "2") (pinfunction "2_2") (pintype "passive"))
      (node (ref "IC4") (pin "12") (pinfunction "O_12") (pintype "open_collector"))
      (node (ref "R56") (pin "2") (pinfunction "2_2") (pintype "passive"))
    )
    (net (code "197") (name "Net-(IC17A-I)") (class "Default")
      (node (ref "C18") (pin "+") (pinfunction "+_+") (pintype "passive"))
      (node (ref "D6") (pin "A") (pinfunction "A_A") (pintype "passive"))
      (node (ref "IC17") (pin "13") (pinfunction "I_13") (pintype "input"))
      (node (ref "R2") (pin "1") (pinfunction "1_1") (pintype "passive"))
      (node (ref "S4") (pin "2") (pinfunction "2_2") (pintype "passive"))
    )
    (net (code "198") (name "Net-(IC17C-I)") (class "Default")
      (node (ref "C19") (pin "+") (pinfunction "+_+") (pintype "passive"))
      (node (ref "D7") (pin "A") (pinfunction "A_A") (pintype "passive"))
      (node (ref "IC17") (pin "9") (pinfunction "I_9") (pintype "input"))
      (node (ref "R3") (pin "2") (pinfunction "2_2") (pintype "passive"))
    )
    (net (code "199") (name "Net-(IC17C-O)") (class "Default")
      (node (ref "IC17") (pin "1") (pinfunction "I_1") (pintype "input"))
      (node (ref "IC17") (pin "8") (pinfunction "O_8") (pintype "output"))
    )
    (net (code "200") (name "Net-(IC17E-I)") (class "Default")
      (node (ref "C22") (pin "1") (pinfunction "1_1") (pintype "passive"))
      (node (ref "D10") (pin "A") (pinfunction "A_A") (pintype "passive"))
      (node (ref "IC17") (pin "3") (pinfunction "I_3") (pintype "input"))
      (node (ref "R6") (pin "1") (pinfunction "1_1") (pintype "passive"))
      (node (ref "S5") (pin "2") (pinfunction "2_2") (pintype "passive"))
    )
    (net (code "201") (name "Net-(IC17F-I)") (class "Default")
      (node (ref "C2") (pin "1") (pinfunction "1_1") (pintype "passive"))
      (node (ref "D4") (pin "A") (pinfunction "A_A") (pintype "passive"))
      (node (ref "IC17") (pin "5") (pinfunction "I_5") (pintype "input"))
      (node (ref "R11") (pin "1") (pinfunction "1_1") (pintype "passive"))
      (node (ref "S2") (pin "2") (pinfunction "2_2") (pintype "passive"))
    )
    (net (code "202") (name "Net-(IC39A-C1+)") (class "Default")
      (node (ref "C38") (pin "2") (pinfunction "2_2") (pintype "passive"))
      (node (ref "IC39") (pin "1") (pinfunction "C1+_1") (pintype "bidirectional"))
    )
    (net (code "203") (name "Net-(IC39A-C1-)") (class "Default")
      (node (ref "C38") (pin "1") (pinfunction "1_1") (pintype "passive"))
      (node (ref "IC39") (pin "3") (pinfunction "C1-_3") (pintype "bidirectional"))
    )
    (net (code "204") (name "Net-(IC39A-C2+)") (class "Default")
      (node (ref "C39") (pin "2") (pinfunction "2_2") (pintype "passive"))
      (node (ref "IC39") (pin "4") (pinfunction "C2+_4") (pintype "bidirectional"))
    )
    (net (code "205") (name "Net-(IC39A-C2-)") (class "Default")
      (node (ref "C39") (pin "1") (pinfunction "1_1") (pintype "passive"))
      (node (ref "IC39") (pin "5") (pinfunction "C2-_5") (pintype "bidirectional"))
    )
    (net (code "206") (name "Net-(IC39A-R1IN)") (class "Default")
      (node (ref "IC39") (pin "13") (pinfunction "R1IN_13") (pintype "input"))
      (node (ref "X2") (pin "3") (pinfunction "3_3") (pintype "passive"))
    )
    (net (code "207") (name "Net-(IC39A-T1OUT)") (class "Default")
      (node (ref "IC39") (pin "14") (pinfunction "T1OUT_14") (pintype "output"))
      (node (ref "X2") (pin "2") (pinfunction "2_2") (pintype "passive"))
    )
    (net (code "208") (name "Net-(IC39A-V+)") (class "Default")
      (node (ref "C37") (pin "1") (pinfunction "1_1") (pintype "passive"))
      (node (ref "IC39") (pin "2") (pinfunction "V+_2") (pintype "bidirectional"))
    )
    (net (code "209") (name "Net-(IC39A-V-)") (class "Default")
      (node (ref "C36") (pin "1") (pinfunction "1_1") (pintype "passive"))
      (node (ref "IC39") (pin "6") (pinfunction "V-_6") (pintype "bidirectional"))
    )
    (net (code "210") (name "unconnected-(CON1-Pad24)") (class "Default")
      (node (ref "CON1") (pin "24") (pinfunction "24_24") (pintype "passive"))
    )
    (net (code "211") (name "unconnected-(CON1-Pad26)") (class "Default")
      (node (ref "CON1") (pin "26") (pinfunction "26_26") (pintype "passive"))
    )
    (net (code "212") (name "unconnected-(CON1-Pad28)") (class "Default")
      (node (ref "CON1") (pin "28") (pinfunction "28_28") (pintype "passive"))
    )
    (net (code "213") (name "unconnected-(CON1-Pad29)") (class "Default")
      (node (ref "CON1") (pin "29") (pinfunction "29_29") (pintype "passive"))
    )
    (net (code "214") (name "unconnected-(CON1B-24-Pad24A)") (class "Default")
      (node (ref "CON1") (pin "24A") (pinfunction "24_24A") (pintype "passive"))
    )
    (net (code "215") (name "unconnected-(CON1B-26-Pad26A)") (class "Default")
      (node (ref "CON1") (pin "26A") (pinfunction "26_26A") (pintype "passive"))
    )
    (net (code "216") (name "unconnected-(CON1B-28-Pad28A)") (class "Default")
      (node (ref "CON1") (pin "28A") (pinfunction "28_28A") (pintype "passive"))
    )
    (net (code "217") (name "unconnected-(CON1B-29-Pad29A)") (class "Default")
      (node (ref "CON1") (pin "29A") (pinfunction "29_29A") (pintype "passive"))
    )
    (net (code "218") (name "unconnected-(CON2-Pad24)") (class "Default")
      (node (ref "CON2") (pin "24") (pinfunction "24_24") (pintype "passive"))
    )
    (net (code "219") (name "unconnected-(CON2-Pad26)") (class "Default")
      (node (ref "CON2") (pin "26") (pinfunction "26_26") (pintype "passive"))
    )
    (net (code "220") (name "unconnected-(CON2-Pad28)") (class "Default")
      (node (ref "CON2") (pin "28") (pinfunction "28_28") (pintype "passive"))
    )
    (net (code "221") (name "unconnected-(CON2-Pad29)") (class "Default")
      (node (ref "CON2") (pin "29") (pinfunction "29_29") (pintype "passive"))
    )
    (net (code "222") (name "unconnected-(CON2B-24-Pad24A)") (class "Default")
      (node (ref "CON2") (pin "24A") (pinfunction "24_24A") (pintype "passive"))
    )
    (net (code "223") (name "unconnected-(CON2B-26-Pad26A)") (class "Default")
      (node (ref "CON2") (pin "26A") (pinfunction "26_26A") (pintype "passive"))
    )
    (net (code "224") (name "unconnected-(CON2B-28-Pad28A)") (class "Default")
      (node (ref "CON2") (pin "28A") (pinfunction "28_28A") (pintype "passive"))
    )
    (net (code "225") (name "unconnected-(CON2B-29-Pad29A)") (class "Default")
      (node (ref "CON2") (pin "29A") (pinfunction "29_29A") (pintype "passive"))
    )
    (net (code "226") (name "unconnected-(DD5-B0-Pad3)") (class "Default")
      (node (ref "DD5") (pin "3") (pinfunction "B0_3") (pintype "bidirectional"))
    )
    (net (code "227") (name "unconnected-(DD5-I0-Pad4)") (class "Default")
      (node (ref "DD5") (pin "4") (pinfunction "I0_4") (pintype "bidirectional"))
    )
    (net (code "228") (name "unconnected-(DD5-O0-Pad2)") (class "Default")
      (node (ref "DD5") (pin "2") (pinfunction "O0_2") (pintype "bidirectional"))
    )
    (net (code "229") (name "unconnected-(DD5-O1-Pad5)") (class "Default")
      (node (ref "DD5") (pin "5") (pinfunction "O1_5") (pintype "bidirectional"))
    )
    (net (code "230") (name "unconnected-(DD5-O2-Pad11)") (class "Default")
      (node (ref "DD5") (pin "11") (pinfunction "O2_11") (pintype "bidirectional"))
    )
    (net (code "231") (name "unconnected-(DD5-O3-Pad14)") (class "Default")
      (node (ref "DD5") (pin "14") (pinfunction "O3_14") (pintype "bidirectional"))
    )
    (net (code "232") (name "unconnected-(DD6-O0-Pad2)") (class "Default")
      (node (ref "DD6") (pin "2") (pinfunction "O0_2") (pintype "bidirectional"))
    )
    (net (code "233") (name "unconnected-(DD6-O1-Pad5)") (class "Default")
      (node (ref "DD6") (pin "5") (pinfunction "O1_5") (pintype "bidirectional"))
    )
    (net (code "234") (name "unconnected-(DD6-O2-Pad11)") (class "Default")
      (node (ref "DD6") (pin "11") (pinfunction "O2_11") (pintype "bidirectional"))
    )
    (net (code "235") (name "unconnected-(DD6-O3-Pad14)") (class "Default")
      (node (ref "DD6") (pin "14") (pinfunction "O3_14") (pintype "bidirectional"))
    )
    (net (code "236") (name "unconnected-(DD7-O0-Pad2)") (class "Default")
      (node (ref "DD7") (pin "2") (pinfunction "O0_2") (pintype "bidirectional"))
    )
    (net (code "237") (name "unconnected-(DD7-O1-Pad5)") (class "Default")
      (node (ref "DD7") (pin "5") (pinfunction "O1_5") (pintype "bidirectional"))
    )
    (net (code "238") (name "unconnected-(DD7-O2-Pad11)") (class "Default")
      (node (ref "DD7") (pin "11") (pinfunction "O2_11") (pintype "bidirectional"))
    )
    (net (code "239") (name "unconnected-(DD7-O3-Pad14)") (class "Default")
      (node (ref "DD7") (pin "14") (pinfunction "O3_14") (pintype "bidirectional"))
    )
    (net (code "240") (name "unconnected-(DD9-B2-Pad10)") (class "Default")
      (node (ref "DD9") (pin "10") (pinfunction "B2_10") (pintype "bidirectional"))
    )
    (net (code "241") (name "unconnected-(DD9-B3-Pad13)") (class "Default")
      (node (ref "DD9") (pin "13") (pinfunction "B3_13") (pintype "bidirectional"))
    )
    (net (code "242") (name "unconnected-(DD9-I2-Pad9)") (class "Default")
      (node (ref "DD9") (pin "9") (pinfunction "I2_9") (pintype "bidirectional"))
    )
    (net (code "243") (name "unconnected-(DD9-I3-Pad12)") (class "Default")
      (node (ref "DD9") (pin "12") (pinfunction "I3_12") (pintype "bidirectional"))
    )
    (net (code "244") (name "unconnected-(DD9-O2-Pad11)") (class "Default")
      (node (ref "DD9") (pin "11") (pinfunction "O2_11") (pintype "bidirectional"))
    )
    (net (code "245") (name "unconnected-(DD9-O3-Pad14)") (class "Default")
      (node (ref "DD9") (pin "14") (pinfunction "O3_14") (pintype "bidirectional"))
    )
    (net (code "246") (name "unconnected-(DD14-I0-Pad4)") (class "Default")
      (node (ref "DD14") (pin "4") (pinfunction "I0_4") (pintype "bidirectional"))
    )
    (net (code "247") (name "unconnected-(DD14-I1-Pad7)") (class "Default")
      (node (ref "DD14") (pin "7") (pinfunction "I1_7") (pintype "bidirectional"))
    )
    (net (code "248") (name "unconnected-(DD14-I2-Pad9)") (class "Default")
      (node (ref "DD14") (pin "9") (pinfunction "I2_9") (pintype "bidirectional"))
    )
    (net (code "249") (name "unconnected-(DD14-I3-Pad12)") (class "Default")
      (node (ref "DD14") (pin "12") (pinfunction "I3_12") (pintype "bidirectional"))
    )
    (net (code "250") (name "unconnected-(DD16-B3-Pad13)") (class "Default")
      (node (ref "DD16") (pin "13") (pinfunction "B3_13") (pintype "bidirectional"))
    )
    (net (code "251") (name "unconnected-(DD16-I3-Pad12)") (class "Default")
      (node (ref "DD16") (pin "12") (pinfunction "I3_12") (pintype "bidirectional"))
    )
    (net (code "252") (name "unconnected-(DD16-O3-Pad14)") (class "Default")
      (node (ref "DD16") (pin "14") (pinfunction "O3_14") (pintype "bidirectional"))
    )
    (net (code "253") (name "unconnected-(IC2-RR-Pad31)") (class "Default")
      (node (ref "IC2") (pin "31") (pinfunction "RR_31") (pintype "bidirectional"))
    )
    (net (code "254") (name "unconnected-(IC2-ST-Pad8)") (class "Default")
      (node (ref "IC2") (pin "8") (pinfunction "ST_8") (pintype "bidirectional"))
    )
    (net (code "255") (name "unconnected-(IC19AS-IO40-Pad112)") (class "Default")
      (node (ref "IC19") (pin "112") (pinfunction "IO40_112") (pintype "bidirectional"))
    )
    (net (code "256") (name "unconnected-(IC19AS-IO48-Pad118)") (class "Default")
      (node (ref "IC19") (pin "118") (pinfunction "IO48_118") (pintype "bidirectional"))
    )
    (net (code "257") (name "unconnected-(IC19AS-IO53-Pad95)") (class "Default")
      (node (ref "IC19") (pin "95") (pinfunction "IO53_95") (pintype "bidirectional"))
    )
    (net (code "258") (name "unconnected-(IC19AS-IO56-Pad97)") (class "Default")
      (node (ref "IC19") (pin "97") (pinfunction "IO56_97") (pintype "bidirectional"))
    )
    (net (code "259") (name "unconnected-(IC19AS-IO57-Pad98)") (class "Default")
      (node (ref "IC19") (pin "98") (pinfunction "IO57_98") (pintype "bidirectional"))
    )
    (net (code "260") (name "unconnected-(IC19AS-IO62-Pad101)") (class "Default")
      (node (ref "IC19") (pin "101") (pinfunction "IO62_101") (pintype "bidirectional"))
    )
    (net (code "261") (name "unconnected-(IC19AS-IO97-Pad119)") (class "Default")
      (node (ref "IC19") (pin "119") (pinfunction "IO97_119") (pintype "bidirectional"))
    )
    (net (code "262") (name "unconnected-(IC19AS-IO107-Pad126)") (class "Default")
      (node (ref "IC19") (pin "126") (pinfunction "IO107_126") (pintype "bidirectional"))
    )
    (net (code "263") (name "unconnected-(IC19AS-IO113-Pad79)") (class "Default")
      (node (ref "IC19") (pin "79") (pinfunction "IO113_79") (pintype "bidirectional"))
    )
    (net (code "264") (name "unconnected-(IC19AS-IO115-Pad80)") (class "Default")
      (node (ref "IC19") (pin "80") (pinfunction "IO115_80") (pintype "bidirectional"))
    )
    (net (code "265") (name "unconnected-(IC19AS-IO121-Pad87)") (class "Default")
      (node (ref "IC19") (pin "87") (pinfunction "IO121_87") (pintype "bidirectional"))
    )
    (net (code "266") (name "unconnected-(IC19AS-IO123-Pad88)") (class "Default")
      (node (ref "IC19") (pin "88") (pinfunction "IO123_88") (pintype "bidirectional"))
    )
    (net (code "267") (name "unconnected-(IC19AS-IO126-Pad90)") (class "Default")
      (node (ref "IC19") (pin "90") (pinfunction "IO126_90") (pintype "bidirectional"))
    )
    (net (code "268") (name "unconnected-(IC19AS-IO145-Pad27)") (class "Default")
      (node (ref "IC19") (pin "27") (pinfunction "IO145_27") (pintype "bidirectional"))
    )
    (net (code "269") (name "unconnected-(IC19AS-IO149-Pad25)") (class "Default")
      (node (ref "IC19") (pin "25") (pinfunction "IO149_25") (pintype "bidirectional"))
    )
    (net (code "270") (name "unconnected-(IC19AS-IO153-Pad21)") (class "Default")
      (node (ref "IC19") (pin "21") (pinfunction "IO153_21") (pintype "bidirectional"))
    )
    (net (code "271") (name "unconnected-(IC19AS-IO155-Pad20)") (class "Default")
      (node (ref "IC19") (pin "20") (pinfunction "IO155_20") (pintype "bidirectional"))
    )
    (net (code "272") (name "unconnected-(IC19AS-IO157-Pad19)") (class "Default")
      (node (ref "IC19") (pin "19") (pinfunction "IO157_19") (pintype "bidirectional"))
    )
    (net (code "273") (name "unconnected-(IC19AS-IO158-Pad18)") (class "Default")
      (node (ref "IC19") (pin "18") (pinfunction "IO158_18") (pintype "bidirectional"))
    )
    (net (code "274") (name "unconnected-(IC19AS-IO160-Pad17)") (class "Default")
      (node (ref "IC19") (pin "17") (pinfunction "IO160_17") (pintype "bidirectional"))
    )
    (net (code "275") (name "unconnected-(IC19AS-IO171-Pad31)") (class "Default")
      (node (ref "IC19") (pin "31") (pinfunction "IO171_31") (pintype "bidirectional"))
    )
    (net (code "276") (name "unconnected-(IC19AS-IO174-Pad29)") (class "Default")
      (node (ref "IC19") (pin "29") (pinfunction "IO174_29") (pintype "bidirectional"))
    )
    (net (code "277") (name "unconnected-(IC19AS-IO189-Pad76)") (class "Default")
      (node (ref "IC19") (pin "76") (pinfunction "IO189_76") (pintype "bidirectional"))
    )
    (net (code "278") (name "unconnected-(IC19AS-IO190-Pad77)") (class "Default")
      (node (ref "IC19") (pin "77") (pinfunction "IO190_77") (pintype "bidirectional"))
    )
    (net (code "279") (name "unconnected-(IC19AS-IO192-Pad78)") (class "Default")
      (node (ref "IC19") (pin "78") (pinfunction "IO192_78") (pintype "bidirectional"))
    )
    (net (code "280") (name "unconnected-(IC19AS-IO193-Pad4)") (class "Default")
      (node (ref "IC19") (pin "4") (pinfunction "IO193_4") (pintype "bidirectional"))
    )
    (net (code "281") (name "unconnected-(IC19AS-IO198-Pad205)") (class "Default")
      (node (ref "IC19") (pin "205") (pinfunction "IO198_205") (pintype "bidirectional"))
    )
    (net (code "282") (name "unconnected-(IC19AS-IO200-Pad204)") (class "Default")
      (node (ref "IC19") (pin "204") (pinfunction "IO200_204") (pintype "bidirectional"))
    )
    (net (code "283") (name "unconnected-(IC19AS-IO201-Pad203)") (class "Default")
      (node (ref "IC19") (pin "203") (pinfunction "IO201_203") (pintype "bidirectional"))
    )
    (net (code "284") (name "unconnected-(IC19AS-IO203-Pad202)") (class "Default")
      (node (ref "IC19") (pin "202") (pinfunction "IO203_202") (pintype "bidirectional"))
    )
    (net (code "285") (name "unconnected-(IC19AS-IO205-Pad201)") (class "Default")
      (node (ref "IC19") (pin "201") (pinfunction "IO205_201") (pintype "bidirectional"))
    )
    (net (code "286") (name "unconnected-(IC19AS-IO213-Pad13)") (class "Default")
      (node (ref "IC19") (pin "13") (pinfunction "IO213_13") (pintype "bidirectional"))
    )
    (net (code "287") (name "unconnected-(IC19AS-IO214-Pad12)") (class "Default")
      (node (ref "IC19") (pin "12") (pinfunction "IO214_12") (pintype "bidirectional"))
    )
    (net (code "288") (name "unconnected-(IC19AS-IO216-Pad11)") (class "Default")
      (node (ref "IC19") (pin "11") (pinfunction "IO216_11") (pintype "bidirectional"))
    )
    (net (code "289") (name "unconnected-(IC19AS-IO217-Pad10)") (class "Default")
      (node (ref "IC19") (pin "10") (pinfunction "IO217_10") (pintype "bidirectional"))
    )
    (net (code "290") (name "unconnected-(IC19AS-IO219-Pad9)") (class "Default")
      (node (ref "IC19") (pin "9") (pinfunction "IO219_9") (pintype "bidirectional"))
    )
    (net (code "291") (name "unconnected-(IC19AS-IO221-Pad8)") (class "Default")
      (node (ref "IC19") (pin "8") (pinfunction "IO221_8") (pintype "bidirectional"))
    )
    (net (code "292") (name "unconnected-(IC19AS-IO222-Pad7)") (class "Default")
      (node (ref "IC19") (pin "7") (pinfunction "IO222_7") (pintype "bidirectional"))
    )
    (net (code "293") (name "unconnected-(IC19AS-IO224-Pad6)") (class "Default")
      (node (ref "IC19") (pin "6") (pinfunction "IO224_6") (pintype "bidirectional"))
    )
    (net (code "294") (name "unconnected-(IC19AS-IO240-Pad39)") (class "Default")
      (node (ref "IC19") (pin "39") (pinfunction "IO240_39") (pintype "bidirectional"))
    )
    (net (code "295") (name "unconnected-(IC19AS-OE2-GCLK2-Pad181)") (class "Default")
      (node (ref "IC19") (pin "181") (pinfunction "OE2-GCLK2_181") (pintype "input"))
    )
    (net (code "296") (name "unconnected-(IC39A-R2IN-Pad8)") (class "Default")
      (node (ref "IC39") (pin "8") (pinfunction "R2IN_8") (pintype "input"))
    )
    (net (code "297") (name "unconnected-(IC39A-R2OUT-Pad9)") (class "Default")
      (node (ref "IC39") (pin "9") (pinfunction "R2OUT_9") (pintype "output"))
    )
    (net (code "298") (name "unconnected-(IC39A-T2IN-Pad10)") (class "Default")
      (node (ref "IC39") (pin "10") (pinfunction "T2IN_10") (pintype "input"))
    )
    (net (code "299") (name "unconnected-(IC39A-T2OUT-Pad7)") (class "Default")
      (node (ref "IC39") (pin "7") (pinfunction "T2OUT_7") (pintype "output"))
    )
    (net (code "300") (name "unconnected-(JP3-Pad6)") (class "Default")
      (node (ref "JP3") (pin "6") (pinfunction "6_6") (pintype "passive"))
    )
    (net (code "301") (name "unconnected-(JP3-Pad7)") (class "Default")
      (node (ref "JP3") (pin "7") (pinfunction "7_7") (pintype "passive"))
    )
    (net (code "302") (name "unconnected-(JP3-Pad8)") (class "Default")
      (node (ref "JP3") (pin "8") (pinfunction "8_8") (pintype "passive"))
    )
    (net (code "303") (name "unconnected-(RN1-Pad7)") (class "Default")
      (node (ref "RN1") (pin "7") (pinfunction "7_7") (pintype "passive"))
    )
    (net (code "304") (name "unconnected-(RN1-Pad8)") (class "Default")
      (node (ref "RN1") (pin "8") (pinfunction "8_8") (pintype "passive"))
    )
    (net (code "305") (name "unconnected-(RN1-Pad9)") (class "Default")
      (node (ref "RN1") (pin "9") (pinfunction "9_9") (pintype "passive"))
    )
    (net (code "306") (name "unconnected-(RN3-Pad8)") (class "Default")
      (node (ref "RN3") (pin "8") (pinfunction "8_8") (pintype "passive"))
    )
    (net (code "307") (name "unconnected-(RN3-Pad9)") (class "Default")
      (node (ref "RN3") (pin "9") (pinfunction "9_9") (pintype "passive"))
    )
    (net (code "308") (name "unconnected-(RN3-Pad10)") (class "Default")
      (node (ref "RN3") (pin "10") (pinfunction "10_10") (pintype "passive"))
    )
    (net (code "309") (name "unconnected-(RN6-Pad5)") (class "Default")
      (node (ref "RN6") (pin "5") (pinfunction "5_5") (pintype "passive"))
    )
    (net (code "310") (name "unconnected-(RN6-Pad6)") (class "Default")
      (node (ref "RN6") (pin "6") (pinfunction "6_6") (pintype "passive"))
    )
    (net (code "311") (name "unconnected-(RN6-Pad7)") (class "Default")
      (node (ref "RN6") (pin "7") (pinfunction "7_7") (pintype "passive"))
    )
    (net (code "312") (name "unconnected-(RN6-Pad8)") (class "Default")
      (node (ref "RN6") (pin "8") (pinfunction "8_8") (pintype "passive"))
    )
    (net (code "313") (name "unconnected-(RN10C-1-Pad4)") (class "Default")
      (node (ref "RN10") (pin "4") (pinfunction "1_4") (pintype "passive"))
    )
    (net (code "314") (name "unconnected-(RN10D-1-Pad5)") (class "Default")
      (node (ref "RN10") (pin "5") (pinfunction "1_5") (pintype "passive"))
    )
    (net (code "315") (name "unconnected-(RN11D-1-Pad5)") (class "Default")
      (node (ref "RN11") (pin "5") (pinfunction "1_5") (pintype "passive"))
    )
    (net (code "316") (name "unconnected-(RN15A-1-Pad2)") (class "Default")
      (node (ref "RN15") (pin "2") (pinfunction "1_2") (pintype "passive"))
    )
    (net (code "317") (name "unconnected-(RN16D-1-Pad5)") (class "Default")
      (node (ref "RN16") (pin "5") (pinfunction "1_5") (pintype "passive"))
    )
    (net (code "318") (name "unconnected-(RN20-Pad9)") (class "Default")
      (node (ref "RN20") (pin "9") (pinfunction "9_9") (pintype "passive"))
    )
    (net (code "319") (name "unconnected-(RN20-Pad10)") (class "Default")
      (node (ref "RN20") (pin "10") (pinfunction "10_10") (pintype "passive"))
    )
    (net (code "320") (name "unconnected-(X2-Pad1)") (class "Default")
      (node (ref "X2") (pin "1") (pinfunction "1_1") (pintype "passive"))
    )
    (net (code "321") (name "unconnected-(X2-Pad4)") (class "Default")
      (node (ref "X2") (pin "4") (pinfunction "4_4") (pintype "passive"))
    )
    (net (code "322") (name "unconnected-(X2-Pad6)") (class "Default")
      (node (ref "X2") (pin "6") (pinfunction "6_6") (pintype "passive"))
    )
    (net (code "323") (name "unconnected-(X2-Pad7)") (class "Default")
      (node (ref "X2") (pin "7") (pinfunction "7_7") (pintype "passive"))
    )
    (net (code "324") (name "unconnected-(X2-Pad8)") (class "Default")
      (node (ref "X2") (pin "8") (pinfunction "8_8") (pintype "passive"))
    )
    (net (code "325") (name "unconnected-(X2-Pad9)") (class "Default")
      (node (ref "X2") (pin "9") (pinfunction "9_9") (pintype "passive"))
    )
    (net (code "326") (name "unconnected-(X2-PadG1)") (class "Default")
      (node (ref "X2") (pin "G1") (pinfunction "G1_G1") (pintype "passive"))
    )
    (net (code "327") (name "unconnected-(XP1A--12-PadAB2)") (class "Default")
      (node (ref "XP1") (pin "AB2") (pinfunction "-12_AB2") (pintype "bidirectional"))
    )
    (net (code "328") (name "unconnected-(XP1A-12V-PadAB4)") (class "Default")
      (node (ref "XP1") (pin "AB4") (pinfunction "12V_AB4") (pintype "bidirectional"))
    )
    (net (code "329") (name "unconnected-(XP1A-P$5-PadAA5)") (class "Default")
      (node (ref "XP1") (pin "AA5") (pinfunction "P$5_AA5") (pintype "bidirectional"))
    )
    (net (code "330") (name "unconnected-(XP1A-P$6-PadAA6)") (class "Default")
      (node (ref "XP1") (pin "AA6") (pinfunction "P$6_AA6") (pintype "bidirectional"))
    )
    (net (code "331") (name "unconnected-(XP1A-P$9-PadAA9)") (class "Default")
      (node (ref "XP1") (pin "AA9") (pinfunction "P$9_AA9") (pintype "bidirectional"))
    )
    (net (code "332") (name "unconnected-(XP1A-P$10-PadAA10)") (class "Default")
      (node (ref "XP1") (pin "AA10") (pinfunction "P$10_AA10") (pintype "bidirectional"))
    )
    (net (code "333") (name "unconnected-(XP1A-P$15-PadAA15)") (class "Default")
      (node (ref "XP1") (pin "AA15") (pinfunction "P$15_AA15") (pintype "bidirectional"))
    )
    (net (code "334") (name "unconnected-(XP1A-P$17-PadAA17)") (class "Default")
      (node (ref "XP1") (pin "AA17") (pinfunction "P$17_AA17") (pintype "bidirectional"))
    )
    (net (code "335") (name "unconnected-(XP1A-{slash}BDMGI-PadAB14)") (class "Default")
      (node (ref "XP1") (pin "AB14") (pinfunction "/BDMGI_AB14") (pintype "bidirectional"))
    )
    (net (code "336") (name "unconnected-(XP1A-{slash}BIAKI-PadAB11)") (class "Default")
      (node (ref "XP1") (pin "AB11") (pinfunction "/BIAKI_AB11") (pintype "bidirectional"))
    )
    (net (code "337") (name "unconnected-(XP1A-{slash}BREF-PadAA14)") (class "Default")
      (node (ref "XP1") (pin "AA14") (pinfunction "/BREF_AA14") (pintype "bidirectional"))
    )
    (net (code "338") (name "unconnected-(XP1B--12-PadBB2)") (class "Default")
      (node (ref "XP1") (pin "BB2") (pinfunction "-12_BB2") (pintype "bidirectional"))
    )
    (net (code "339") (name "unconnected-(XP1B-12V-PadBB4)") (class "Default")
      (node (ref "XP1") (pin "BB4") (pinfunction "12V_BB4") (pintype "bidirectional"))
    )
    (net (code "340") (name "unconnected-(XP1B-P$9-PadBA9)") (class "Default")
      (node (ref "XP1") (pin "BA9") (pinfunction "P$9_BA9") (pintype "bidirectional"))
    )
    (net (code "341") (name "unconnected-(XP1B-P$10-PadBA10)") (class "Default")
      (node (ref "XP1") (pin "BA10") (pinfunction "P$10_BA10") (pintype "bidirectional"))
    )
    (net (code "342") (name "unconnected-(XP1B-P$15-PadBA15)") (class "Default")
      (node (ref "XP1") (pin "BA15") (pinfunction "P$15_BA15") (pintype "bidirectional"))
    )
    (net (code "343") (name "unconnected-(XP1B-P$17-PadBA17)") (class "Default")
      (node (ref "XP1") (pin "BA17") (pinfunction "P$17_BA17") (pintype "bidirectional"))
    )
  )
)
